# zigduino-r3a.net
KiCad netlist of a schematic drawn in EAGLE
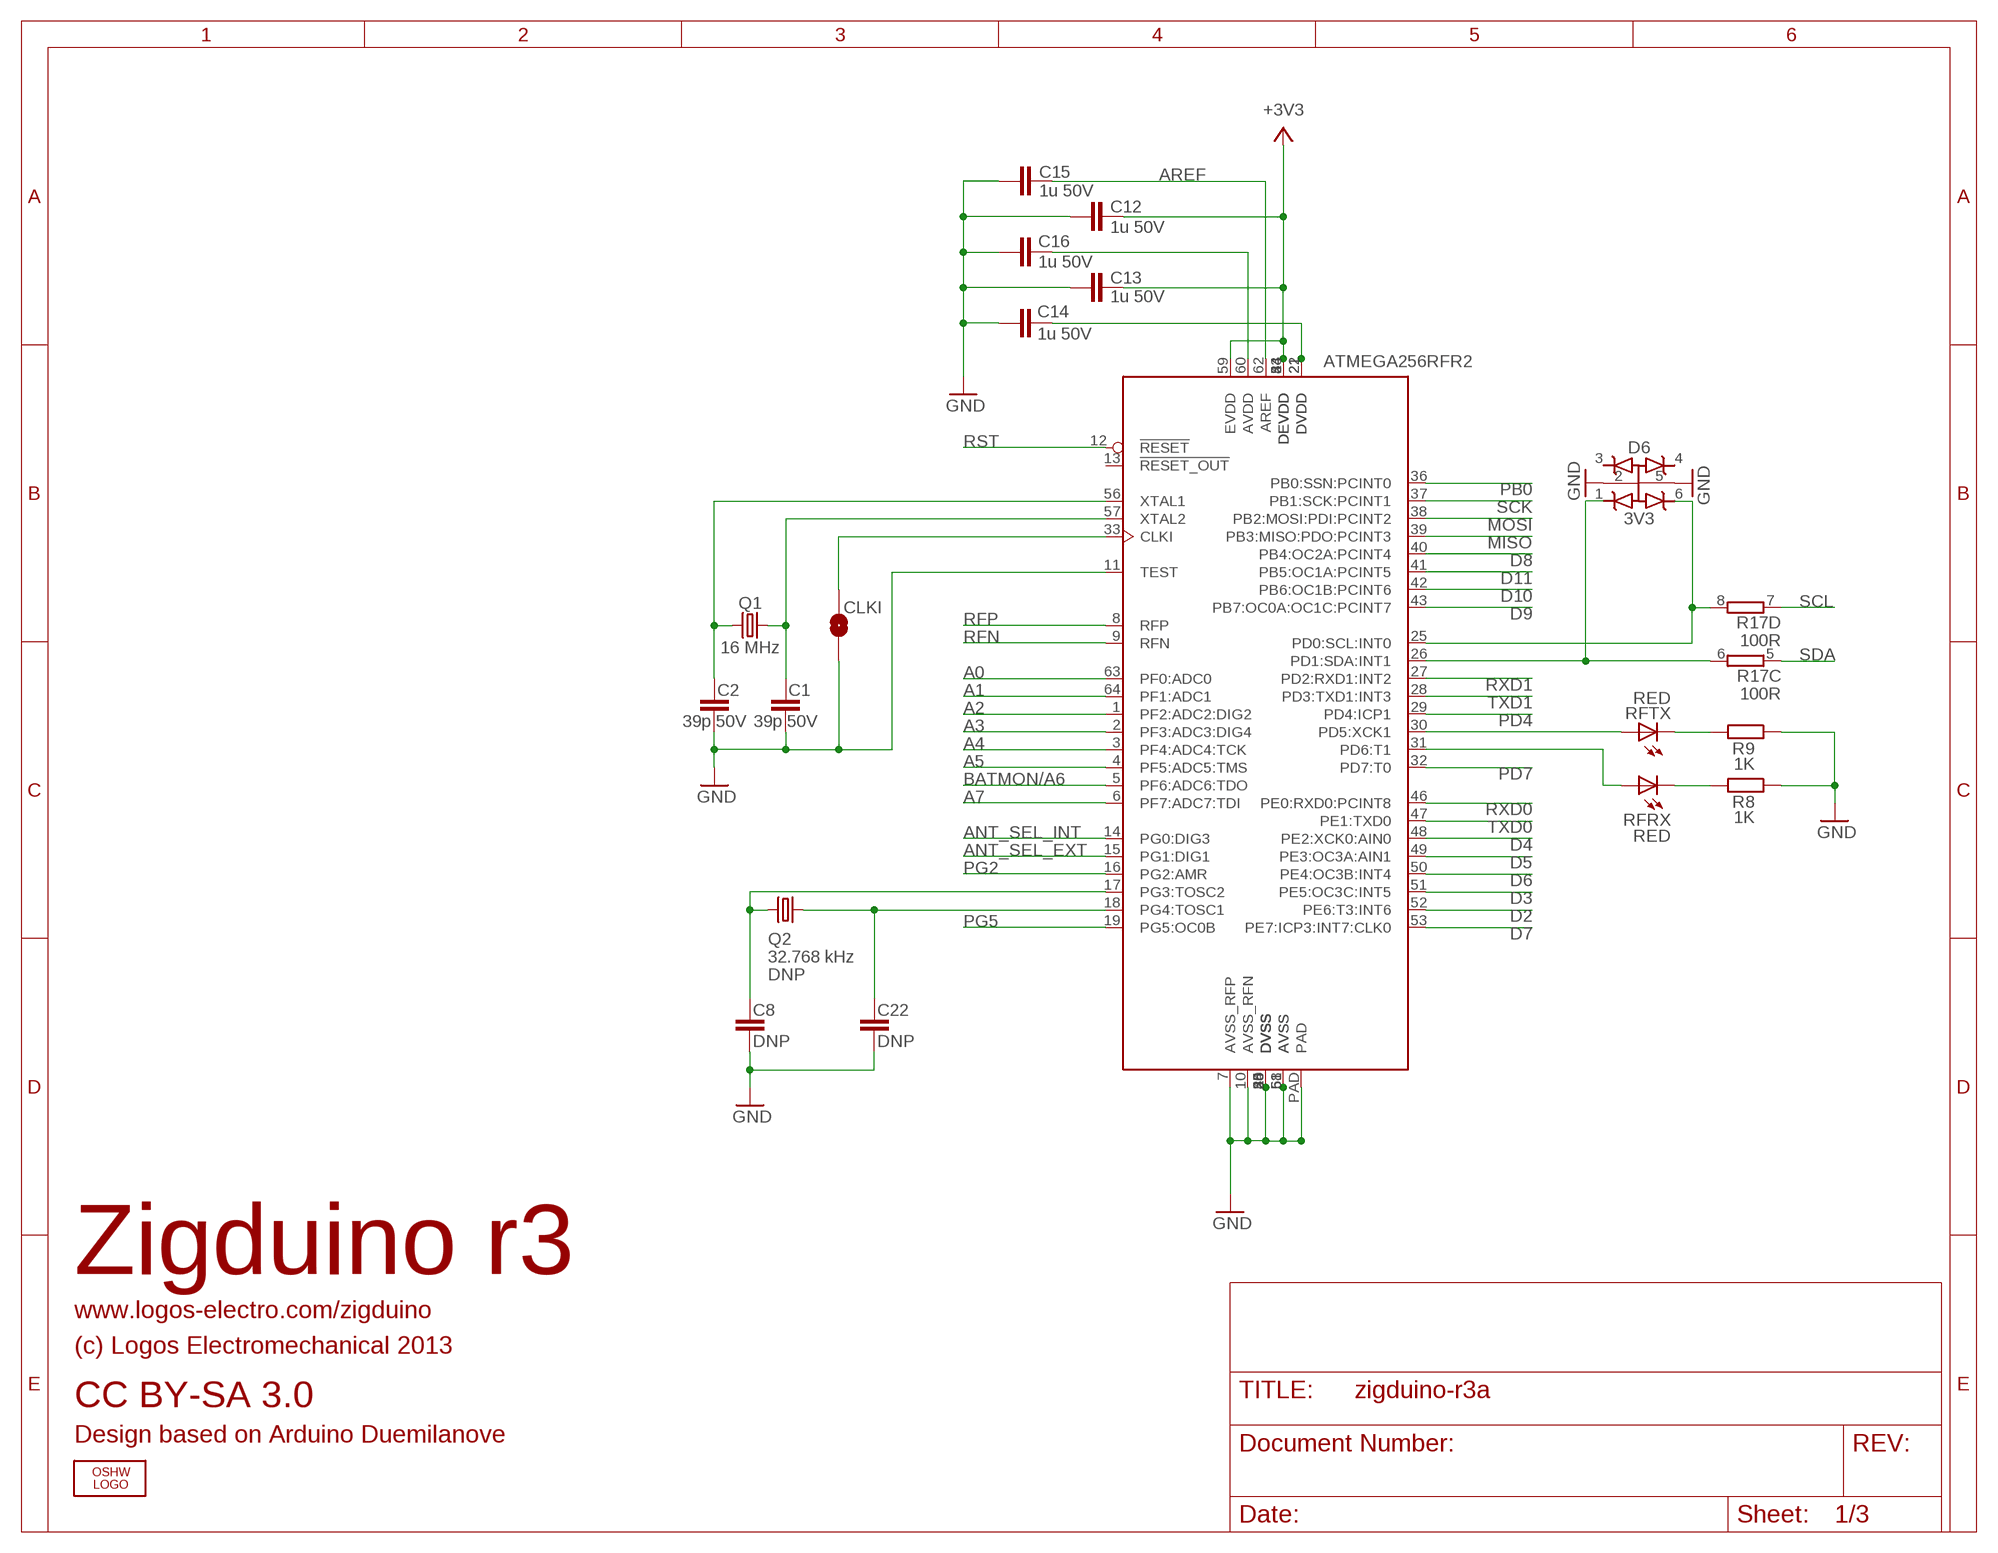
[diagram p0: schematic, sheet 1]
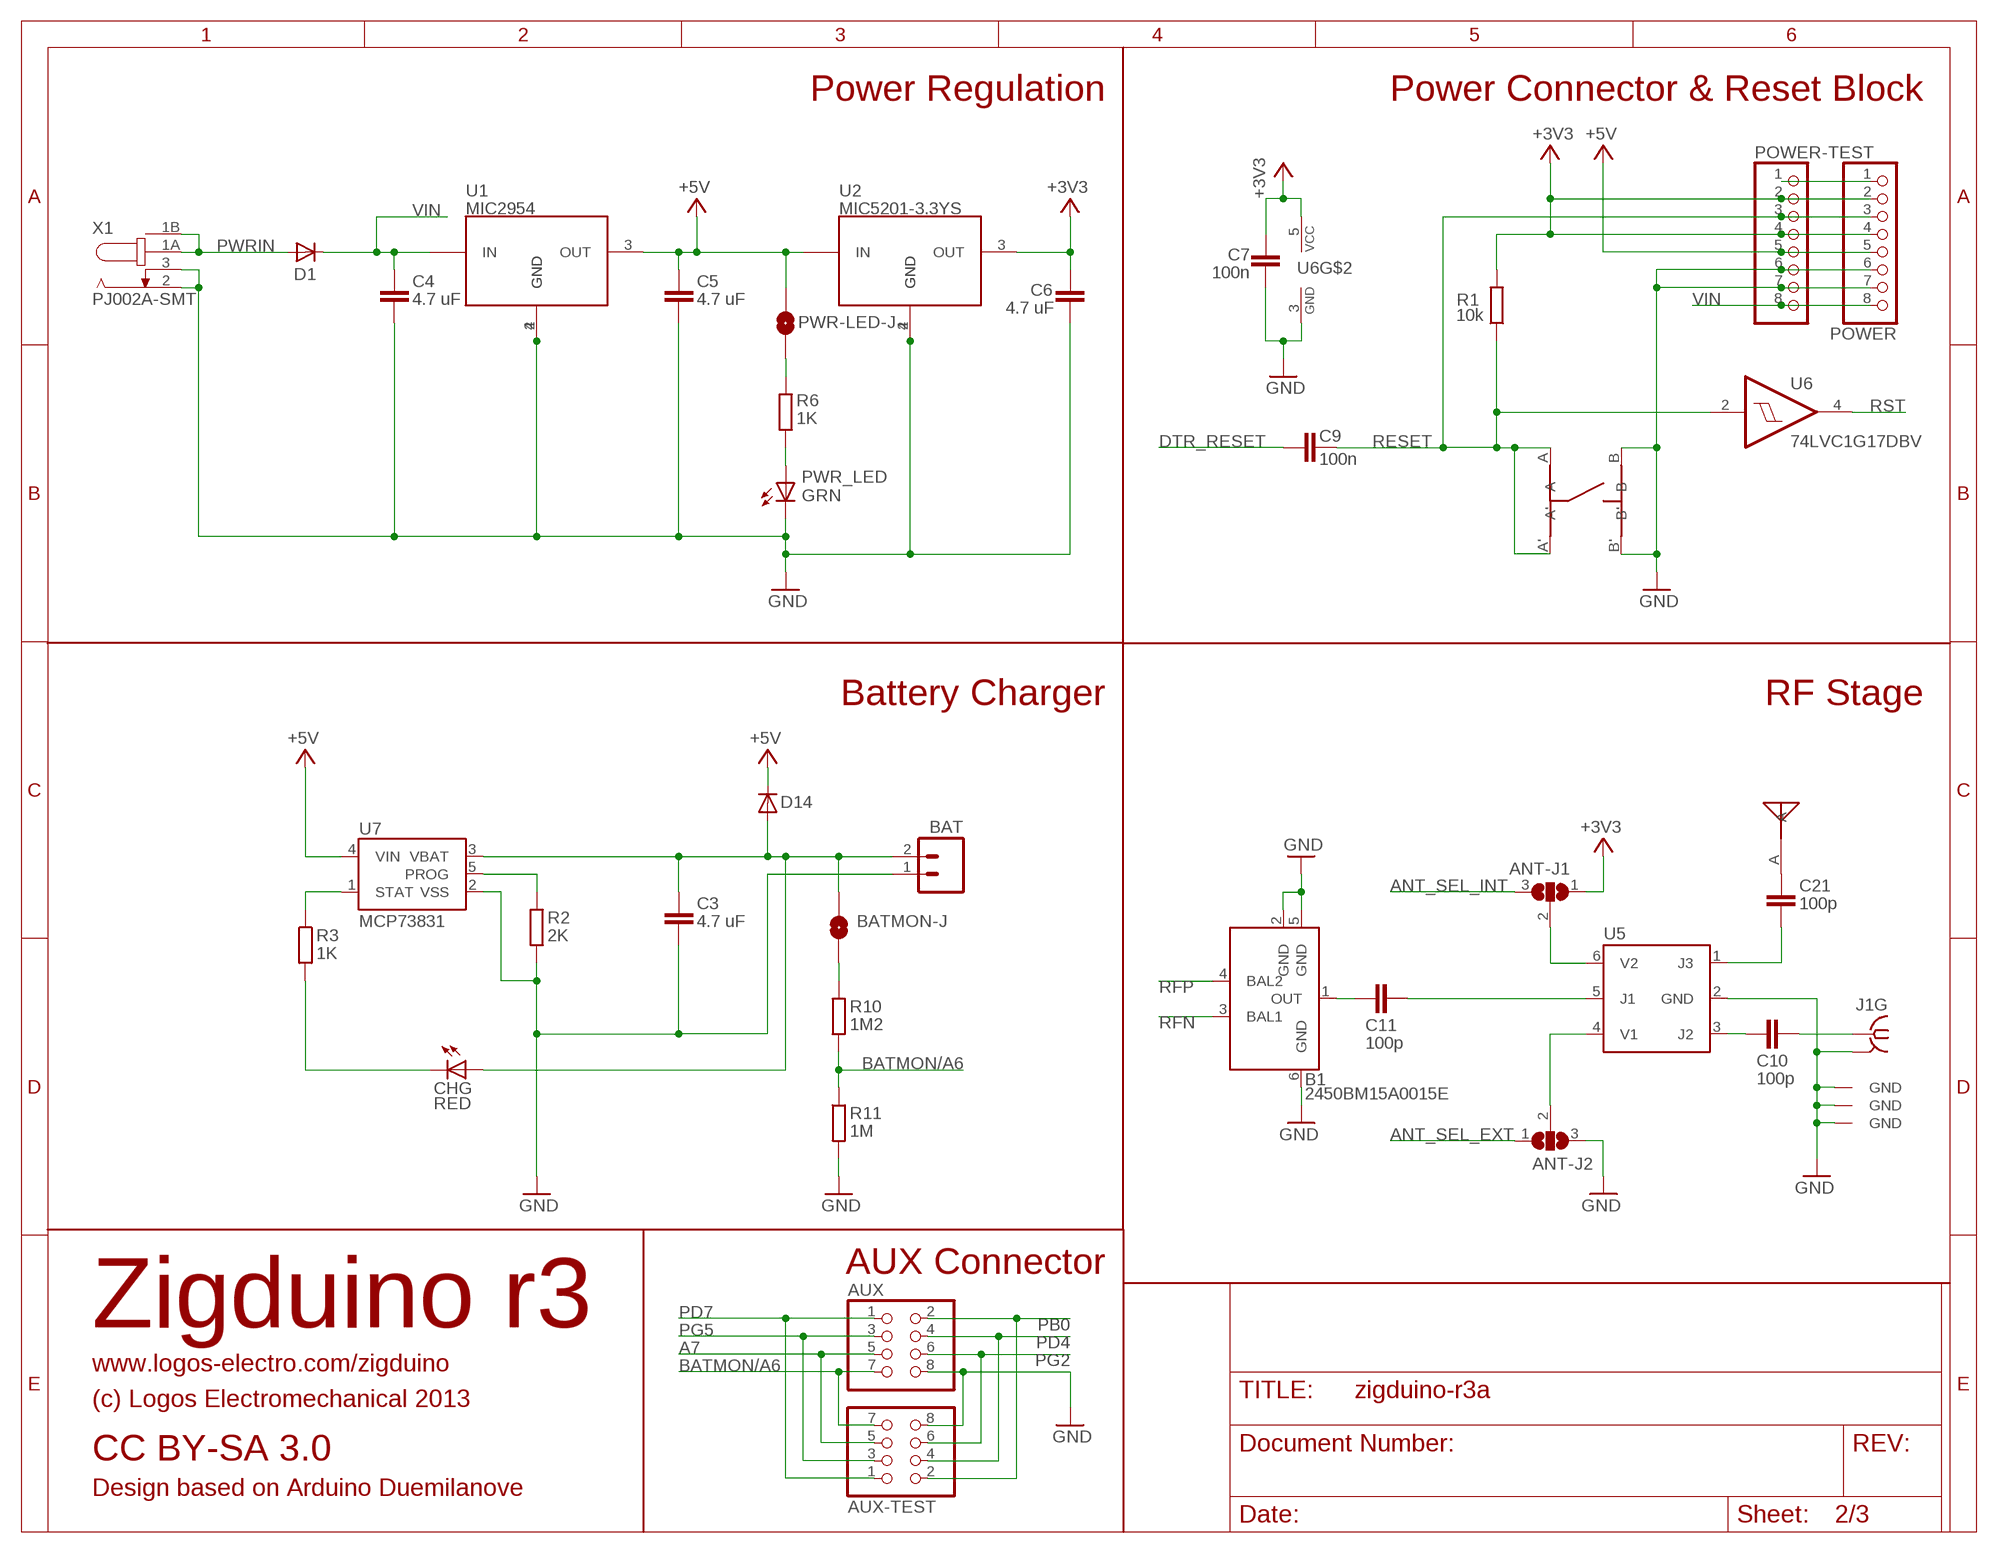
[diagram p1: schematic, sheet 2]
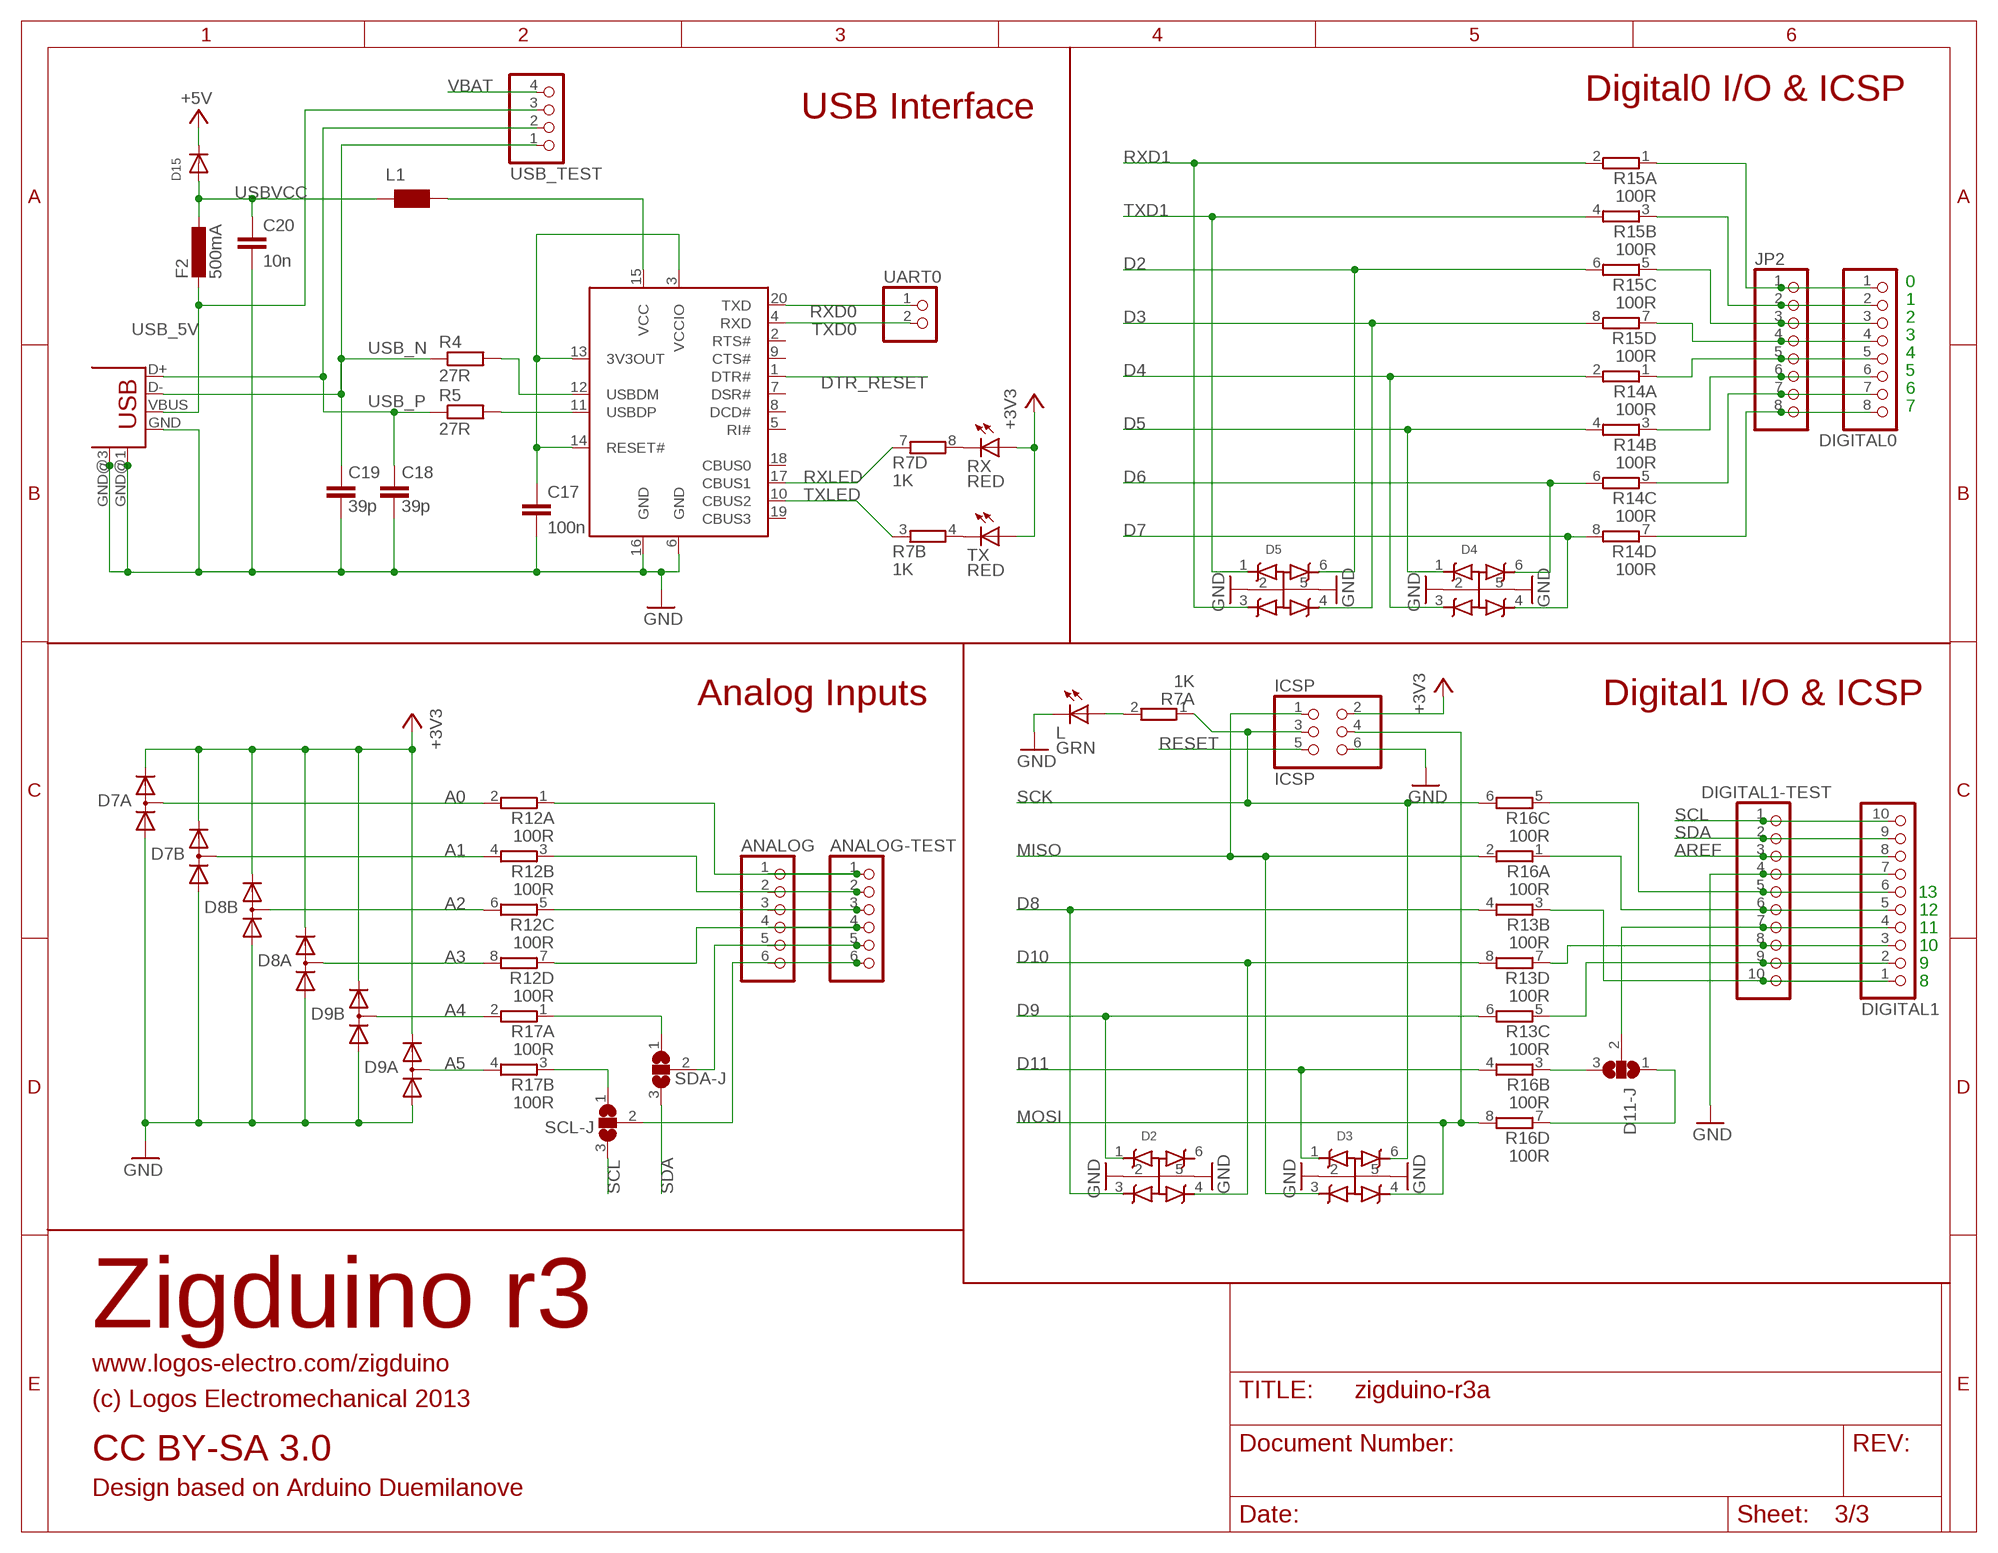
[diagram p2: schematic, sheet 3]

(export (version "E")
  (design (tool "Eeschema 10.0.6"))
  (components
    (comp (ref "ANT-J1")
      (value "SOLDERJUMPER_2WAYSHORT1&2")
      (footprint "eagle-import:SJ_3_SHORT1&2")
      (libsource (lib "eagle-import") (part "SOLDERJUMPER_2WAYSHORT1&2"))
    )
    (comp (ref "ANT-J2")
      (value "SOLDERJUMPER_2WAYSHORT2&3")
      (footprint "eagle-import:SJ_3_SHORT2&3")
      (libsource (lib "eagle-import") (part "SOLDERJUMPER_2WAYSHORT2&3"))
    )
    (comp (ref "ANT1")
      (value "MOLEX-ANT")
      (footprint "eagle-import:MOLEX-ANT")
      (fields (field (name "PARTNO") "0479480001"))
      (libsource (lib "eagle-import") (part "MOLEX-ANT"))
    )
    (comp (ref "AUX")
      (value "PINHD-2X4_2.54-SMD")
      (footprint "eagle-import:2X04SMD")
      (libsource (lib "eagle-import") (part "PINHD-2X4_2.54-SMD"))
    )
    (comp (ref "AUX-TEST")
      (value "PINHD-2X4TEST")
      (footprint "eagle-import:2X04-TEST")
      (libsource (lib "eagle-import") (part "PINHD-2X4TEST"))
    )
    (comp (ref "B1")
      (value "2450BM15A0015E")
      (footprint "eagle-import:WURTH-BALUN")
      (libsource (lib "eagle-import") (part "2450BM15A0015E"))
    )
    (comp (ref "BAT")
      (value "M02-JST-2MM-SMT")
      (footprint "eagle-import:S2B-PH")
      (fields (field (name "PARTNO") "S2B-PH-SM4-TB(LF)(SN)"))
      (libsource (lib "eagle-import") (part "M02-JST-2MM-SMT"))
    )
    (comp (ref "BATMON-J")
      (value "SOLDERJUMPERTRACE")
      (footprint "eagle-import:SJ_2S-TRACE")
      (libsource (lib "eagle-import") (part "SOLDERJUMPERTRACE"))
    )
    (comp (ref "C3")
      (value "4.7 uF")
      (footprint "eagle-import:C1206")
      (fields (field (name "PARTNO") "C3216Y5V1H475Z"))
      (libsource (lib "eagle-import") (part "C-EUC1206"))
    )
    (comp (ref "C4")
      (value "4.7 uF")
      (footprint "eagle-import:C1206")
      (fields (field (name "PARTNO") "C3216Y5V1H475Z"))
      (libsource (lib "eagle-import") (part "C-EUC1206"))
    )
    (comp (ref "C5")
      (value "4.7 uF")
      (footprint "eagle-import:C1206")
      (fields (field (name "PARTNO") "C3216Y5V1H475Z"))
      (libsource (lib "eagle-import") (part "C-EUC1206"))
    )
    (comp (ref "C6")
      (value "4.7 uF")
      (footprint "eagle-import:C1206")
      (fields (field (name "PARTNO") "C3216Y5V1H475Z"))
      (libsource (lib "eagle-import") (part "C-EUC1206"))
    )
    (comp (ref "C7")
      (value "100n")
      (footprint "eagle-import:C0603")
      (fields (field (name "PARTNO") "CC0603MRY5V9BB104"))
      (libsource (lib "eagle-import") (part "C-EUC0603"))
    )
    (comp (ref "C9")
      (value "100n")
      (footprint "eagle-import:C0603")
      (fields (field (name "PARTNO") "CC0603MRY5V9BB104"))
      (libsource (lib "eagle-import") (part "C-EUC0603"))
    )
    (comp (ref "C10")
      (value "100p")
      (footprint "eagle-import:C0603")
      (libsource (lib "eagle-import") (part "C-EUC0603"))
    )
    (comp (ref "C11")
      (value "100p")
      (footprint "eagle-import:C0603")
      (libsource (lib "eagle-import") (part "C-EUC0603"))
    )
    (comp (ref "C21")
      (value "100p")
      (footprint "eagle-import:C0603")
      (libsource (lib "eagle-import") (part "C-EUC0603"))
    )
    (comp (ref "CHG")
      (value "RED")
      (footprint "eagle-import:CHIP-LED0603")
      (fields (field (name "PARTNO") "LTST-C193KRKT-5A"))
      (libsource (lib "eagle-import") (part "LEDCHIP-LED0603"))
    )
    (comp (ref "D1")
      (value "DIODESOD-123")
      (footprint "eagle-import:SOD-123")
      (fields (field (name "PARTNO") "B150B-13-F"))
      (libsource (lib "eagle-import") (part "DIODESOD-123"))
    )
    (comp (ref "D14")
      (value "DIODESOD-123")
      (footprint "eagle-import:SOD-123")
      (fields (field (name "PARTNO") "B150B-13-F"))
      (libsource (lib "eagle-import") (part "DIODESOD-123"))
    )
    (comp (ref "J1")
      (value "CONNREVSMA003.062")
      (footprint "eagle-import:EDGE-RSMA")
      (libsource (lib "eagle-import") (part "CONNREVSMA003.062"))
    )
    (comp (ref "POWER")
      (value "PINHD-1X8_2.54-SMD")
      (footprint "eagle-import:1X08SMD")
      (fields (field (name "PARTNO") "19743"))
      (libsource (lib "eagle-import") (part "PINHD-1X8_2.54-SMD"))
    )
    (comp (ref "POWER-TEST")
      (value "PINHD-1X8TEST")
      (footprint "eagle-import:1X08-TEST")
      (libsource (lib "eagle-import") (part "PINHD-1X8TEST"))
    )
    (comp (ref "PWR-LED-J")
      (value "SOLDERJUMPERTRACE")
      (footprint "eagle-import:SJ_2S-TRACE")
      (libsource (lib "eagle-import") (part "SOLDERJUMPERTRACE"))
    )
    (comp (ref "PWR_LED")
      (value "GRN")
      (footprint "eagle-import:CHIP-LED0603")
      (fields (field (name "PARTNO") "LTST-C193KGKT-5A"))
      (libsource (lib "eagle-import") (part "LEDCHIP-LED0603"))
    )
    (comp (ref "R1")
      (value "10k")
      (footprint "eagle-import:R0603")
      (fields (field (name "PARTNO") "RMCF0603FT10K0"))
      (libsource (lib "eagle-import") (part "R-EU_R0603"))
    )
    (comp (ref "R2")
      (value "2K")
      (footprint "eagle-import:R0603")
      (fields (field (name "PARTNO") "RC0603FR-072KL"))
      (libsource (lib "eagle-import") (part "R-EU_R0603"))
    )
    (comp (ref "R3")
      (value "1K")
      (footprint "eagle-import:R0603")
      (fields (field (name "PARTNO") "RMCF0603FT1K00"))
      (libsource (lib "eagle-import") (part "R-EU_R0603"))
    )
    (comp (ref "R6")
      (value "1K")
      (footprint "eagle-import:R0603")
      (fields (field (name "PARTNO") "RMCF0603FT1K00"))
      (libsource (lib "eagle-import") (part "R-EU_R0603"))
    )
    (comp (ref "R10")
      (value "1M2")
      (footprint "eagle-import:R0603")
      (fields (field (name "PARTNO") "ERJ-3EKF1204V"))
      (libsource (lib "eagle-import") (part "R-EU_R0603"))
    )
    (comp (ref "R11")
      (value "1M")
      (footprint "eagle-import:R0603")
      (fields (field (name "PARTNO") "ERJ-3EKF1004V"))
      (libsource (lib "eagle-import") (part "R-EU_R0603"))
    )
    (comp (ref "SW1")
      (value "EVQ-PSD02K")
      (footprint "eagle-import:EVQPSD02K")
      (libsource (lib "eagle-import") (part "EVQ-PSD02K"))
    )
    (comp (ref "U1")
      (value "MIC2954")
      (footprint "eagle-import:SOT223")
      (fields (field (name "PARTNO") "MIC2954-03WS-TR"))
      (libsource (lib "eagle-import") (part "MIC2954"))
    )
    (comp (ref "U2")
      (value "MIC5201-3.3YS")
      (footprint "eagle-import:SOT223")
      (fields (field (name "PARTNO") "MIC5201-3.3YS TR"))
      (libsource (lib "eagle-import") (part "MIC5201-3.3BS"))
    )
    (comp (ref "U5")
      (value "AS222-92LF")
      (footprint "eagle-import:SC70-6L")
      (libsource (lib "eagle-import") (part "AS222-92LF"))
    )
    (comp (ref "U6")
      (value "74LVC1G17DBV")
      (footprint "eagle-import:SOT23-5")
      (fields (field (name "PARTNO") "SN74LVC1G17DBVR") (field (name "BOM") "INCLUDE"))
      (libsource (lib "eagle-import") (part "741G17DBVLVC"))
    )
    (comp (ref "U7")
      (value "MCP73831")
      (footprint "eagle-import:SOT23-5")
      (fields (field (name "PARTNO") "MCP73831T-2ACI/OT"))
      (libsource (lib "eagle-import") (part "MCP73831"))
    )
    (comp (ref "X1")
      (value "PJ002A-SMT")
      (footprint "eagle-import:PJ002A-SMT")
      (fields (field (name "PARTNO") "PJ-002AH-SMT"))
      (libsource (lib "eagle-import") (part "PJ002A-SMT"))
    )
    (comp (ref "ANALOG")
      (value "PINHD-1X6_2.54-SMD")
      (footprint "eagle-import:1X06SMD")
      (fields (field (name "PARTNO") "19742"))
      (libsource (lib "eagle-import") (part "PINHD-1X6_2.54-SMD"))
    )
    (comp (ref "ANALOG-TEST")
      (value "PINHD-1X6TEST")
      (footprint "eagle-import:1X06-TEST")
      (libsource (lib "eagle-import") (part "PINHD-1X6TEST"))
    )
    (comp (ref "C17")
      (value "100n")
      (footprint "eagle-import:C0603")
      (fields (field (name "PARTNO") "CC0603MRY5V9BB104"))
      (libsource (lib "eagle-import") (part "C-EUC0603"))
    )
    (comp (ref "C18")
      (value "39p")
      (footprint "eagle-import:C0603")
      (fields (field (name "PARTNO") "C1608C0G1H390J"))
      (libsource (lib "eagle-import") (part "C-EUC0603"))
    )
    (comp (ref "C19")
      (value "39p")
      (footprint "eagle-import:C0603")
      (fields (field (name "PARTNO") "C1608C0G1H390J"))
      (libsource (lib "eagle-import") (part "C-EUC0603"))
    )
    (comp (ref "C20")
      (value "10n")
      (footprint "eagle-import:C0603")
      (fields (field (name "PARTNO") "GRM188R71H103KA01D"))
      (libsource (lib "eagle-import") (part "C-EUC0603"))
    )
    (comp (ref "D2")
      (value "PESD3V3S4UD")
      (footprint "eagle-import:SC74_INFINEON")
      (libsource (lib "eagle-import") (part "PESD3V3S4UD"))
    )
    (comp (ref "D3")
      (value "PESD3V3S4UD")
      (footprint "eagle-import:SC74_INFINEON")
      (libsource (lib "eagle-import") (part "PESD3V3S4UD"))
    )
    (comp (ref "D4")
      (value "PESD3V3S4UD")
      (footprint "eagle-import:SC74_INFINEON")
      (libsource (lib "eagle-import") (part "PESD3V3S4UD"))
    )
    (comp (ref "D5")
      (value "PESD3V3S4UD")
      (footprint "eagle-import:SC74_INFINEON")
      (libsource (lib "eagle-import") (part "PESD3V3S4UD"))
    )
    (comp (ref "D7")
      (value "SD103ASDM")
      (footprint "eagle-import:SOT26")
      (fields
        (field (name "BOM") "INCLUDE")
        (field (name "PARTNO") "SD103ASDM-7")
        (field (name "VOLT") "40V")
      )
      (libsource (lib "eagle-import") (part "SD103ASDM"))
    )
    (comp (ref "D8")
      (value "SD103ASDM")
      (footprint "eagle-import:SOT26")
      (fields
        (field (name "PARTNO") "SD103ASDM-7")
        (field (name "BOM") "INCLUDE")
        (field (name "VOLT") "40V")
      )
      (libsource (lib "eagle-import") (part "SD103ASDM"))
    )
    (comp (ref "D9")
      (value "SD103ASDM")
      (footprint "eagle-import:SOT26")
      (fields
        (field (name "PARTNO") "SD103ASDM-7")
        (field (name "BOM") "INCLUDE")
        (field (name "VOLT") "40V")
      )
      (libsource (lib "eagle-import") (part "SD103ASDM"))
    )
    (comp (ref "D11-J")
      (value "SOLDERJUMPER_2WAYSHORT2&3")
      (footprint "eagle-import:SJ_3_SHORT2&3")
      (libsource (lib "eagle-import") (part "SOLDERJUMPER_2WAYSHORT2&3"))
    )
    (comp (ref "D15")
      (value "DIODESOD-123")
      (footprint "eagle-import:SOD-123")
      (fields (field (name "PARTNO") "B150B-13-F"))
      (libsource (lib "eagle-import") (part "DIODESOD-123"))
    )
    (comp (ref "DIGITAL0")
      (value "PINHD-1X8_2.54-SMD")
      (footprint "eagle-import:1X08SMD")
      (fields (field (name "PARTNO") "19743"))
      (libsource (lib "eagle-import") (part "PINHD-1X8_2.54-SMD"))
    )
    (comp (ref "DIGITAL1")
      (value "PINHD-1X10_2.54-SMD")
      (footprint "eagle-import:1X10SMD")
      (fields (field (name "PARTNO") "20083"))
      (libsource (lib "eagle-import") (part "PINHD-1X10_2.54-SMD"))
    )
    (comp (ref "DIGITAL1-TEST")
      (value "PINHD-1X10TEST")
      (footprint "eagle-import:1X10-TEST")
      (libsource (lib "eagle-import") (part "PINHD-1X10TEST"))
    )
    (comp (ref "F2")
      (value "500mA")
      (footprint "eagle-import:L1812")
      (fields (field (name "PARTNO") "MF-MSMF050-2"))
      (libsource (lib "eagle-import") (part "L-EUL1812"))
    )
    (comp (ref "ICSP")
      (value "ICSP")
      (footprint "eagle-import:2X03")
      (fields (field (name "PARTNO") "961206-6404-AR"))
      (libsource (lib "eagle-import") (part "PINHD-2X3"))
    )
    (comp (ref "JP2")
      (value "PINHD-1X8TEST")
      (footprint "eagle-import:1X08-TEST")
      (libsource (lib "eagle-import") (part "PINHD-1X8TEST"))
    )
    (comp (ref "L")
      (value "GRN")
      (footprint "eagle-import:CHIP-LED0603")
      (fields (field (name "PARTNO") "LTST-C193KGKT-5A"))
      (libsource (lib "eagle-import") (part "LEDCHIP-LED0603"))
    )
    (comp (ref "L1")
      (value "WE-CBF_0805")
      (footprint "eagle-import:0805")
      (fields (field (name "PARTNO") "MI0805K400R-10"))
      (libsource (lib "eagle-import") (part "WE-CBF_0805"))
    )
    (comp (ref "R4")
      (value "27R")
      (footprint "eagle-import:R0603")
      (fields (field (name "PARTNO") "RC0603JR-0727RL"))
      (libsource (lib "eagle-import") (part "R-EU_R0603"))
    )
    (comp (ref "R5")
      (value "27R")
      (footprint "eagle-import:R0603")
      (fields (field (name "PARTNO") "RC0603JR-0727RL"))
      (libsource (lib "eagle-import") (part "R-EU_R0603"))
    )
    (comp (ref "R7")
      (value "1K")
      (footprint "eagle-import:CTS742C083-RES")
      (fields (field (name "BOM") "INCLUDE") (field (name "PARTNO") "742C083102JPTR"))
      (libsource (lib "eagle-import") (part "4R-NCTS742C083"))
    )
    (comp (ref "R12")
      (value "100R")
      (footprint "eagle-import:CTS742C083-RES")
      (fields (field (name "BOM") "INCLUDE") (field (name "PARTNO") "742C083101JPTR"))
      (libsource (lib "eagle-import") (part "4R-NCTS742C083"))
    )
    (comp (ref "R13")
      (value "100R")
      (footprint "eagle-import:CTS742C083-RES")
      (fields (field (name "BOM") "INCLUDE") (field (name "PARTNO") "742C083101JPTR"))
      (libsource (lib "eagle-import") (part "4R-NCTS742C083"))
    )
    (comp (ref "R14")
      (value "100R")
      (footprint "eagle-import:CTS742C083-RES")
      (fields (field (name "BOM") "INCLUDE") (field (name "PARTNO") "742C083101JPTR"))
      (libsource (lib "eagle-import") (part "4R-NCTS742C083"))
    )
    (comp (ref "R15")
      (value "100R")
      (footprint "eagle-import:CTS742C083-RES")
      (fields (field (name "BOM") "INCLUDE") (field (name "PARTNO") "742C083101JPTR"))
      (libsource (lib "eagle-import") (part "4R-NCTS742C083"))
    )
    (comp (ref "R16")
      (value "100R")
      (footprint "eagle-import:CTS742C083-RES")
      (fields (field (name "BOM") "INCLUDE") (field (name "PARTNO") "742C083101JPTR"))
      (libsource (lib "eagle-import") (part "4R-NCTS742C083"))
    )
    (comp (ref "R17")
      (value "100R")
      (footprint "eagle-import:CTS742C083-RES")
      (fields (field (name "PARTNO") "742C083101JPTR") (field (name "BOM") "INCLUDE"))
      (libsource (lib "eagle-import") (part "4R-NCTS742C083"))
    )
    (comp (ref "RX")
      (value "RED")
      (footprint "eagle-import:CHIP-LED0603")
      (fields (field (name "PARTNO") "LTST-C193KRKT-5A"))
      (libsource (lib "eagle-import") (part "LEDCHIP-LED0603"))
    )
    (comp (ref "SCL-J")
      (value "SOLDERJUMPER_2WAYSHORT2&3")
      (footprint "eagle-import:SJ_3_SHORT2&3")
      (libsource (lib "eagle-import") (part "SOLDERJUMPER_2WAYSHORT2&3"))
    )
    (comp (ref "SDA-J")
      (value "SOLDERJUMPER_2WAYSHORT2&3")
      (footprint "eagle-import:SJ_3_SHORT2&3")
      (libsource (lib "eagle-import") (part "SOLDERJUMPER_2WAYSHORT2&3"))
    )
    (comp (ref "TX")
      (value "RED")
      (footprint "eagle-import:CHIP-LED0603")
      (fields (field (name "PARTNO") "LTST-C193KRKT-5A"))
      (libsource (lib "eagle-import") (part "LEDCHIP-LED0603"))
    )
    (comp (ref "U4")
      (value "FT231XS-R")
      (footprint "eagle-import:SSOP20")
      (libsource (lib "eagle-import") (part "FT231XS-R"))
    )
    (comp (ref "UART0")
      (value "PINHD-1X2")
      (footprint "eagle-import:1X02")
      (fields (field (name "PARTNO") "00522"))
      (libsource (lib "eagle-import") (part "PINHD-1X2"))
    )
    (comp (ref "USB")
      (value "USB-MB-S")
      (footprint "eagle-import:USB-MB-S")
      (fields (field (name "PARTNO") "20236"))
      (libsource (lib "eagle-import") (part "USB-MB-S"))
    )
    (comp (ref "USB_TEST")
      (value "PINHD-1X4TEST")
      (footprint "eagle-import:1X04-TEST")
      (libsource (lib "eagle-import") (part "PINHD-1X4TEST"))
    )
    (comp (ref "C1")
      (value "39p 50V")
      (footprint "eagle-import:C0603")
      (fields (field (name "PARTNO") "C1608C0G1H390J"))
      (libsource (lib "eagle-import") (part "C-EUC0603"))
    )
    (comp (ref "C2")
      (value "39p 50V")
      (footprint "eagle-import:C0603")
      (fields (field (name "PARTNO") "C1608C0G1H390J"))
      (libsource (lib "eagle-import") (part "C-EUC0603"))
    )
    (comp (ref "C8")
      (value "DNP")
      (footprint "eagle-import:C0603")
      (libsource (lib "eagle-import") (part "C-EUC0603"))
    )
    (comp (ref "C12")
      (value "1u 50V")
      (footprint "eagle-import:C0603")
      (libsource (lib "eagle-import") (part "C-EUC0603"))
    )
    (comp (ref "C13")
      (value "1u 50V")
      (footprint "eagle-import:C0603")
      (libsource (lib "eagle-import") (part "C-EUC0603"))
    )
    (comp (ref "C14")
      (value "1u 50V")
      (footprint "eagle-import:C0603")
      (libsource (lib "eagle-import") (part "C-EUC0603"))
    )
    (comp (ref "C15")
      (value "1u 50V")
      (footprint "eagle-import:C0603")
      (libsource (lib "eagle-import") (part "C-EUC0603"))
    )
    (comp (ref "C16")
      (value "1u 50V")
      (footprint "eagle-import:C0603")
      (libsource (lib "eagle-import") (part "C-EUC0603"))
    )
    (comp (ref "C22")
      (value "DNP")
      (footprint "eagle-import:C0603")
      (libsource (lib "eagle-import") (part "C-EUC0603"))
    )
    (comp (ref "CLKI")
      (value "SOLDERJUMPERTRACE")
      (footprint "eagle-import:SJ_2S-TRACE")
      (libsource (lib "eagle-import") (part "SOLDERJUMPERTRACE"))
    )
    (comp (ref "D6")
      (value "3V3")
      (footprint "eagle-import:SC74_INFINEON")
      (libsource (lib "eagle-import") (part "PESD3V3S4UD"))
    )
    (comp (ref "LOGO1")
      (value "OSHW_LOGO_FILLX0200-NT")
      (footprint "eagle-import:OSHW_FILLX200_NOTEXT")
      (libsource (lib "eagle-import") (part "OSHW_LOGO_FILLX0200-NT"))
    )
    (comp (ref "Q1")
      (value "16 MHz")
      (footprint "eagle-import:CSM-3X")
      (fields (field (name "PARTNO") "ECS-160-20-3X-TR"))
      (libsource (lib "eagle-import") (part "CRYSTALCSM-3X"))
    )
    (comp (ref "Q2")
      (value "32.768 kHz")
      (footprint "eagle-import:TC26H")
      (libsource (lib "eagle-import") (part "CRYSTALTC26H"))
    )
    (comp (ref "R8")
      (value "1K")
      (footprint "eagle-import:R0603")
      (fields (field (name "PARTNO") "RMCF0603FT1K00"))
      (libsource (lib "eagle-import") (part "R-EU_R0603"))
    )
    (comp (ref "R9")
      (value "1K")
      (footprint "eagle-import:R0603")
      (fields (field (name "PARTNO") "RMCF0603FT1K00"))
      (libsource (lib "eagle-import") (part "R-EU_R0603"))
    )
    (comp (ref "RFRX")
      (value "RED")
      (footprint "eagle-import:CHIP-LED0603")
      (fields (field (name "PARTNO") "LTST-C193KRKT-5A"))
      (libsource (lib "eagle-import") (part "LEDCHIP-LED0603"))
    )
    (comp (ref "RFTX")
      (value "RED")
      (footprint "eagle-import:CHIP-LED0603")
      (fields (field (name "PARTNO") "LTST-C193KRKT-5A"))
      (libsource (lib "eagle-import") (part "LEDCHIP-LED0603"))
    )
    (comp (ref "U3")
      (value "ATMEGA128RFA1")
      (footprint "eagle-import:QFN64")
      (fields (field (name "PARTNO") "ATMEGA128RFA1-ZUR"))
      (libsource (lib "eagle-import") (part "ATMEGA128RFA1"))
    )
  )
  (nets
    (net (code "1") (name "+3V3") (class "Default")
      (node (ref "ANT-J1") (pin "1") (pinfunction "1_1") (pintype "passive"))
      (node (ref "C12") (pin "1") (pinfunction "1_1") (pintype "passive"))
      (node (ref "C13") (pin "1") (pinfunction "1_1") (pintype "passive"))
      (node (ref "C6") (pin "1") (pinfunction "1_1") (pintype "passive"))
      (node (ref "C7") (pin "2") (pinfunction "2_2") (pintype "passive"))
      (node (ref "D7") (pin "2") (pinfunction "C_2") (pintype "passive"))
      (node (ref "D7") (pin "5") (pinfunction "C_5") (pintype "passive"))
      (node (ref "D8") (pin "2") (pinfunction "C_2") (pintype "passive"))
      (node (ref "D8") (pin "5") (pinfunction "C_5") (pintype "passive"))
      (node (ref "D9") (pin "2") (pinfunction "C_2") (pintype "passive"))
      (node (ref "D9") (pin "5") (pinfunction "C_5") (pintype "passive"))
      (node (ref "ICSP") (pin "2") (pinfunction "2_2") (pintype "passive"))
      (node (ref "POWER") (pin "2") (pinfunction "2_2") (pintype "passive"))
      (node (ref "POWER") (pin "4") (pinfunction "4_4") (pintype "passive"))
      (node (ref "POWER-TEST") (pin "2") (pinfunction "2_2") (pintype "passive"))
      (node (ref "POWER-TEST") (pin "4") (pinfunction "4_4") (pintype "passive"))
      (node (ref "R1") (pin "2") (pinfunction "2_2") (pintype "passive"))
      (node (ref "RX") (pin "A") (pinfunction "A_A") (pintype "passive"))
      (node (ref "TX") (pin "A") (pinfunction "A_A") (pintype "passive"))
      (node (ref "U2") (pin "3") (pinfunction "OUT_3") (pintype "bidirectional"))
      (node (ref "U3") (pin "23") (pinfunction "DEVDD_23") (pintype "bidirectional"))
      (node (ref "U3") (pin "34") (pinfunction "DEVDD_34") (pintype "bidirectional"))
      (node (ref "U3") (pin "44") (pinfunction "DEVDD_44") (pintype "bidirectional"))
      (node (ref "U3") (pin "54") (pinfunction "DEVDD_54") (pintype "bidirectional"))
      (node (ref "U3") (pin "59") (pinfunction "EVDD_59") (pintype "bidirectional"))
      (node (ref "U6") (pin "5") (pinfunction "VCC_5") (pintype "power_in"))
    )
    (net (code "2") (name "+5V") (class "Default")
      (node (ref "C5") (pin "1") (pinfunction "1_1") (pintype "passive"))
      (node (ref "D14") (pin "C") (pinfunction "C_C") (pintype "passive"))
      (node (ref "D15") (pin "C") (pinfunction "C_C") (pintype "passive"))
      (node (ref "POWER") (pin "5") (pinfunction "5_5") (pintype "passive"))
      (node (ref "POWER-TEST") (pin "5") (pinfunction "5_5") (pintype "passive"))
      (node (ref "PWR-LED-J") (pin "2") (pinfunction "2_2") (pintype "passive"))
      (node (ref "U1") (pin "3") (pinfunction "OUT_3") (pintype "bidirectional"))
      (node (ref "U2") (pin "1") (pinfunction "IN_1") (pintype "bidirectional"))
      (node (ref "U7") (pin "4") (pinfunction "VIN_4") (pintype "power_in"))
    )
    (net (code "3") (name "A0") (class "Default")
      (node (ref "D7") (pin "4") (pinfunction "AC_4") (pintype "passive"))
      (node (ref "R12") (pin "2") (pinfunction "2_2") (pintype "passive"))
      (node (ref "U3") (pin "63") (pinfunction "PF0:ADC0_63") (pintype "bidirectional"))
    )
    (net (code "4") (name "A1") (class "Default")
      (node (ref "D7") (pin "1") (pinfunction "AC_1") (pintype "passive"))
      (node (ref "R12") (pin "4") (pinfunction "2_4") (pintype "passive"))
      (node (ref "U3") (pin "64") (pinfunction "PF1:ADC1_64") (pintype "bidirectional"))
    )
    (net (code "5") (name "A2") (class "Default")
      (node (ref "D8") (pin "1") (pinfunction "AC_1") (pintype "passive"))
      (node (ref "R12") (pin "6") (pinfunction "2_6") (pintype "passive"))
      (node (ref "U3") (pin "1") (pinfunction "PF2:ADC2:DIG2_1") (pintype "bidirectional"))
    )
    (net (code "6") (name "A3") (class "Default")
      (node (ref "D8") (pin "4") (pinfunction "AC_4") (pintype "passive"))
      (node (ref "R12") (pin "8") (pinfunction "2_8") (pintype "passive"))
      (node (ref "U3") (pin "2") (pinfunction "PF3:ADC3:DIG4_2") (pintype "bidirectional"))
    )
    (net (code "7") (name "A4") (class "Default")
      (node (ref "D9") (pin "1") (pinfunction "AC_1") (pintype "passive"))
      (node (ref "R17") (pin "2") (pinfunction "2_2") (pintype "passive"))
      (node (ref "U3") (pin "3") (pinfunction "PF4:ADC4:TCK_3") (pintype "bidirectional"))
    )
    (net (code "8") (name "A5") (class "Default")
      (node (ref "D9") (pin "4") (pinfunction "AC_4") (pintype "passive"))
      (node (ref "R17") (pin "4") (pinfunction "2_4") (pintype "passive"))
      (node (ref "U3") (pin "4") (pinfunction "PF5:ADC5:TMS_4") (pintype "bidirectional"))
    )
    (net (code "9") (name "A7") (class "Default")
      (node (ref "AUX") (pin "5") (pinfunction "5_5") (pintype "passive"))
      (node (ref "AUX-TEST") (pin "5") (pinfunction "5_5") (pintype "passive"))
      (node (ref "U3") (pin "6") (pinfunction "PF7:ADC7:TDI_6") (pintype "bidirectional"))
    )
    (net (code "10") (name "ANT_SEL_EXT") (class "Default")
      (node (ref "ANT-J2") (pin "1") (pinfunction "1_1") (pintype "passive"))
      (node (ref "U3") (pin "15") (pinfunction "PG1:DIG1_15") (pintype "bidirectional"))
    )
    (net (code "11") (name "ANT_SEL_INT") (class "Default")
      (node (ref "ANT-J1") (pin "3") (pinfunction "3_3") (pintype "passive"))
      (node (ref "U3") (pin "14") (pinfunction "PG0:DIG3_14") (pintype "bidirectional"))
    )
    (net (code "12") (name "AREF") (class "Default")
      (node (ref "C15") (pin "2") (pinfunction "2_2") (pintype "passive"))
      (node (ref "DIGITAL1") (pin "8") (pinfunction "8_8") (pintype "passive"))
      (node (ref "DIGITAL1-TEST") (pin "3") (pinfunction "3_3") (pintype "passive"))
      (node (ref "U3") (pin "62") (pinfunction "AREF_62") (pintype "bidirectional"))
    )
    (net (code "13") (name "BATMON{slash}A6") (class "Default")
      (node (ref "AUX") (pin "7") (pinfunction "7_7") (pintype "passive"))
      (node (ref "AUX-TEST") (pin "7") (pinfunction "7_7") (pintype "passive"))
      (node (ref "R10") (pin "2") (pinfunction "2_2") (pintype "passive"))
      (node (ref "R11") (pin "1") (pinfunction "1_1") (pintype "passive"))
      (node (ref "U3") (pin "5") (pinfunction "PF6:ADC6:TDO_5") (pintype "bidirectional"))
    )
    (net (code "14") (name "D2") (class "Default")
      (node (ref "D5") (pin "6") (pinfunction "Z6_6") (pintype "bidirectional"))
      (node (ref "R15") (pin "6") (pinfunction "2_6") (pintype "passive"))
      (node (ref "U3") (pin "52") (pinfunction "PE6:T3:INT6_52") (pintype "bidirectional"))
    )
    (net (code "15") (name "D3") (class "Default")
      (node (ref "D5") (pin "4") (pinfunction "Z4_4") (pintype "bidirectional"))
      (node (ref "R15") (pin "8") (pinfunction "2_8") (pintype "passive"))
      (node (ref "U3") (pin "51") (pinfunction "PE5:OC3C:INT5_51") (pintype "bidirectional"))
    )
    (net (code "16") (name "D4") (class "Default")
      (node (ref "D4") (pin "3") (pinfunction "Z3_3") (pintype "bidirectional"))
      (node (ref "R14") (pin "2") (pinfunction "2_2") (pintype "passive"))
      (node (ref "U3") (pin "48") (pinfunction "PE2:XCK0:AIN0_48") (pintype "bidirectional"))
    )
    (net (code "17") (name "D5") (class "Default")
      (node (ref "D4") (pin "1") (pinfunction "Z1_1") (pintype "bidirectional"))
      (node (ref "R14") (pin "4") (pinfunction "2_4") (pintype "passive"))
      (node (ref "U3") (pin "49") (pinfunction "PE3:OC3A:AIN1_49") (pintype "bidirectional"))
    )
    (net (code "18") (name "D6") (class "Default")
      (node (ref "D4") (pin "6") (pinfunction "Z6_6") (pintype "bidirectional"))
      (node (ref "R14") (pin "6") (pinfunction "2_6") (pintype "passive"))
      (node (ref "U3") (pin "50") (pinfunction "PE4:OC3B:INT4_50") (pintype "bidirectional"))
    )
    (net (code "19") (name "D7") (class "Default")
      (node (ref "D4") (pin "4") (pinfunction "Z4_4") (pintype "bidirectional"))
      (node (ref "R14") (pin "8") (pinfunction "2_8") (pintype "passive"))
      (node (ref "U3") (pin "53") (pinfunction "PE7:ICP3:INT7:CLK0_53") (pintype "bidirectional"))
    )
    (net (code "20") (name "D8") (class "Default")
      (node (ref "D2") (pin "3") (pinfunction "Z3_3") (pintype "bidirectional"))
      (node (ref "R13") (pin "4") (pinfunction "2_4") (pintype "passive"))
      (node (ref "U3") (pin "40") (pinfunction "PB4:OC2A:PCINT4_40") (pintype "bidirectional"))
    )
    (net (code "21") (name "D9") (class "Default")
      (node (ref "D2") (pin "1") (pinfunction "Z1_1") (pintype "bidirectional"))
      (node (ref "R13") (pin "6") (pinfunction "2_6") (pintype "passive"))
      (node (ref "U3") (pin "43") (pinfunction "PB7:OC0A:OC1C:PCINT7_43") (pintype "bidirectional"))
    )
    (net (code "22") (name "D10") (class "Default")
      (node (ref "D2") (pin "4") (pinfunction "Z4_4") (pintype "bidirectional"))
      (node (ref "R13") (pin "8") (pinfunction "2_8") (pintype "passive"))
      (node (ref "U3") (pin "42") (pinfunction "PB6:OC1B:PCINT6_42") (pintype "bidirectional"))
    )
    (net (code "23") (name "D11") (class "Default")
      (node (ref "D3") (pin "1") (pinfunction "Z1_1") (pintype "bidirectional"))
      (node (ref "R16") (pin "4") (pinfunction "2_4") (pintype "passive"))
      (node (ref "U3") (pin "41") (pinfunction "PB5:OC1A:PCINT5_41") (pintype "bidirectional"))
    )
    (net (code "24") (name "DTR_RESET") (class "Default")
      (node (ref "C9") (pin "1") (pinfunction "1_1") (pintype "passive"))
      (node (ref "U4") (pin "1") (pinfunction "DTR#_1") (pintype "bidirectional"))
    )
    (net (code "25") (name "GND") (class "Default")
      (node (ref "ANT-J2") (pin "3") (pinfunction "3_3") (pintype "passive"))
      (node (ref "AUX") (pin "8") (pinfunction "8_8") (pintype "passive"))
      (node (ref "AUX-TEST") (pin "8") (pinfunction "8_8") (pintype "passive"))
      (node (ref "B1") (pin "2") (pinfunction "GND_2") (pintype "bidirectional"))
      (node (ref "B1") (pin "5") (pinfunction "GND_5") (pintype "bidirectional"))
      (node (ref "B1") (pin "6") (pinfunction "GND_6") (pintype "bidirectional"))
      (node (ref "BAT") (pin "1") (pinfunction "1_1") (pintype "passive"))
      (node (ref "C1") (pin "1") (pinfunction "1_1") (pintype "passive"))
      (node (ref "C12") (pin "2") (pinfunction "2_2") (pintype "passive"))
      (node (ref "C13") (pin "2") (pinfunction "2_2") (pintype "passive"))
      (node (ref "C14") (pin "2") (pinfunction "2_2") (pintype "passive"))
      (node (ref "C15") (pin "1") (pinfunction "1_1") (pintype "passive"))
      (node (ref "C16") (pin "1") (pinfunction "1_1") (pintype "passive"))
      (node (ref "C17") (pin "2") (pinfunction "2_2") (pintype "passive"))
      (node (ref "C18") (pin "2") (pinfunction "2_2") (pintype "passive"))
      (node (ref "C19") (pin "2") (pinfunction "2_2") (pintype "passive"))
      (node (ref "C2") (pin "1") (pinfunction "1_1") (pintype "passive"))
      (node (ref "C20") (pin "2") (pinfunction "2_2") (pintype "passive"))
      (node (ref "C22") (pin "1") (pinfunction "1_1") (pintype "passive"))
      (node (ref "C3") (pin "2") (pinfunction "2_2") (pintype "passive"))
      (node (ref "C4") (pin "2") (pinfunction "2_2") (pintype "passive"))
      (node (ref "C5") (pin "2") (pinfunction "2_2") (pintype "passive"))
      (node (ref "C6") (pin "2") (pinfunction "2_2") (pintype "passive"))
      (node (ref "C7") (pin "1") (pinfunction "1_1") (pintype "passive"))
      (node (ref "C8") (pin "1") (pinfunction "1_1") (pintype "passive"))
      (node (ref "CLKI") (pin "2") (pinfunction "2_2") (pintype "passive"))
      (node (ref "D2") (pin "2") (pinfunction "G2_2") (pintype "bidirectional"))
      (node (ref "D2") (pin "5") (pinfunction "G5_5") (pintype "bidirectional"))
      (node (ref "D3") (pin "2") (pinfunction "G2_2") (pintype "bidirectional"))
      (node (ref "D3") (pin "5") (pinfunction "G5_5") (pintype "bidirectional"))
      (node (ref "D4") (pin "2") (pinfunction "G2_2") (pintype "bidirectional"))
      (node (ref "D4") (pin "5") (pinfunction "G5_5") (pintype "bidirectional"))
      (node (ref "D5") (pin "2") (pinfunction "G2_2") (pintype "bidirectional"))
      (node (ref "D5") (pin "5") (pinfunction "G5_5") (pintype "bidirectional"))
      (node (ref "D6") (pin "2") (pinfunction "G2_2") (pintype "bidirectional"))
      (node (ref "D6") (pin "5") (pinfunction "G5_5") (pintype "bidirectional"))
      (node (ref "D7") (pin "3") (pinfunction "A_3") (pintype "passive"))
      (node (ref "D7") (pin "6") (pinfunction "A_6") (pintype "passive"))
      (node (ref "D8") (pin "3") (pinfunction "A_3") (pintype "passive"))
      (node (ref "D8") (pin "6") (pinfunction "A_6") (pintype "passive"))
      (node (ref "D9") (pin "3") (pinfunction "A_3") (pintype "passive"))
      (node (ref "D9") (pin "6") (pinfunction "A_6") (pintype "passive"))
      (node (ref "DIGITAL1") (pin "7") (pinfunction "7_7") (pintype "passive"))
      (node (ref "DIGITAL1-TEST") (pin "4") (pinfunction "4_4") (pintype "passive"))
      (node (ref "ICSP") (pin "6") (pinfunction "6_6") (pintype "passive"))
      (node (ref "J1") (pin "SHIELD@0") (pinfunction "GND_SHIELD@0") (pintype "power_in"))
      (node (ref "J1") (pin "SHIELD@1") (pinfunction "GND_SHIELD@1") (pintype "power_in"))
      (node (ref "J1") (pin "SHIELD@2") (pinfunction "GND_SHIELD@2") (pintype "power_in"))
      (node (ref "J1") (pin "SHIELD@3") (pinfunction "GND_SHIELD@3") (pintype "power_in"))
      (node (ref "L") (pin "C") (pinfunction "C_C") (pintype "passive"))
      (node (ref "POWER") (pin "6") (pinfunction "6_6") (pintype "passive"))
      (node (ref "POWER") (pin "7") (pinfunction "7_7") (pintype "passive"))
      (node (ref "POWER-TEST") (pin "6") (pinfunction "6_6") (pintype "passive"))
      (node (ref "POWER-TEST") (pin "7") (pinfunction "7_7") (pintype "passive"))
      (node (ref "PWR_LED") (pin "C") (pinfunction "C_C") (pintype "passive"))
      (node (ref "R11") (pin "2") (pinfunction "2_2") (pintype "passive"))
      (node (ref "R2") (pin "1") (pinfunction "1_1") (pintype "passive"))
      (node (ref "R8") (pin "1") (pinfunction "1_1") (pintype "passive"))
      (node (ref "R9") (pin "1") (pinfunction "1_1") (pintype "passive"))
      (node (ref "SW1") (pin "B") (pinfunction "B_B") (pintype "bidirectional"))
      (node (ref "SW1") (pin "B'") (pinfunction "B'_B'") (pintype "bidirectional"))
      (node (ref "U1") (pin "2") (pinfunction "GND_2") (pintype "bidirectional"))
      (node (ref "U1") (pin "4") (pinfunction "GND_4") (pintype "bidirectional"))
      (node (ref "U2") (pin "2") (pinfunction "GND_2") (pintype "bidirectional"))
      (node (ref "U2") (pin "4") (pinfunction "GND_4") (pintype "bidirectional"))
      (node (ref "U3") (pin "10") (pinfunction "AVSS_RFN_10") (pintype "bidirectional"))
      (node (ref "U3") (pin "11") (pinfunction "TEST_11") (pintype "bidirectional"))
      (node (ref "U3") (pin "20") (pinfunction "DVSS_20") (pintype "bidirectional"))
      (node (ref "U3") (pin "24") (pinfunction "DVSS_24") (pintype "bidirectional"))
      (node (ref "U3") (pin "35") (pinfunction "DVSS_35") (pintype "bidirectional"))
      (node (ref "U3") (pin "45") (pinfunction "DVSS_45") (pintype "bidirectional"))
      (node (ref "U3") (pin "55") (pinfunction "DVSS_55") (pintype "bidirectional"))
      (node (ref "U3") (pin "58") (pinfunction "AVSS_58") (pintype "bidirectional"))
      (node (ref "U3") (pin "61") (pinfunction "AVSS_61") (pintype "bidirectional"))
      (node (ref "U3") (pin "7") (pinfunction "AVSS_RFP_7") (pintype "bidirectional"))
      (node (ref "U3") (pin "PAD") (pinfunction "PAD_PAD") (pintype "bidirectional"))
      (node (ref "U4") (pin "16") (pinfunction "GND_16") (pintype "bidirectional"))
      (node (ref "U4") (pin "6") (pinfunction "GND_6") (pintype "bidirectional"))
      (node (ref "U5") (pin "2") (pinfunction "GND_2") (pintype "bidirectional"))
      (node (ref "U6") (pin "3") (pinfunction "GND_3") (pintype "power_in"))
      (node (ref "U7") (pin "2") (pinfunction "VSS_2") (pintype "power_in"))
      (node (ref "USB") (pin "GND") (pinfunction "GND_GND") (pintype "bidirectional"))
      (node (ref "USB") (pin "GND@1") (pinfunction "GND_GND@1") (pintype "bidirectional"))
      (node (ref "USB") (pin "GND@3") (pinfunction "GND_GND@3") (pintype "bidirectional"))
      (node (ref "X1") (pin "2") (pinfunction "2_2") (pintype "passive"))
      (node (ref "X1") (pin "3") (pinfunction "3_3") (pintype "passive"))
    )
    (net (code "26") (name "MISO") (class "Default")
      (node (ref "D3") (pin "3") (pinfunction "Z3_3") (pintype "bidirectional"))
      (node (ref "ICSP") (pin "1") (pinfunction "1_1") (pintype "passive"))
      (node (ref "R16") (pin "2") (pinfunction "2_2") (pintype "passive"))
      (node (ref "U3") (pin "39") (pinfunction "PB3:MISO:PDO:PCINT3_39") (pintype "bidirectional"))
    )
    (net (code "27") (name "MOSI") (class "Default")
      (node (ref "D3") (pin "4") (pinfunction "Z4_4") (pintype "bidirectional"))
      (node (ref "ICSP") (pin "4") (pinfunction "4_4") (pintype "passive"))
      (node (ref "R16") (pin "8") (pinfunction "2_8") (pintype "passive"))
      (node (ref "U3") (pin "38") (pinfunction "PB2:MOSI:PDI:PCINT2_38") (pintype "bidirectional"))
    )
    (net (code "28") (name "Net-(ANALOG-Pad1)") (class "Default")
      (node (ref "ANALOG") (pin "1") (pinfunction "1_1") (pintype "passive"))
      (node (ref "ANALOG-TEST") (pin "1") (pinfunction "1_1") (pintype "passive"))
      (node (ref "R12") (pin "1") (pinfunction "1_1") (pintype "passive"))
    )
    (net (code "29") (name "Net-(ANALOG-Pad5)") (class "Default")
      (node (ref "ANALOG") (pin "5") (pinfunction "5_5") (pintype "passive"))
      (node (ref "ANALOG-TEST") (pin "5") (pinfunction "5_5") (pintype "passive"))
      (node (ref "SDA-J") (pin "2") (pinfunction "2_2") (pintype "passive"))
    )
    (net (code "30") (name "Net-(ANALOG-Pad6)") (class "Default")
      (node (ref "ANALOG") (pin "6") (pinfunction "6_6") (pintype "passive"))
      (node (ref "ANALOG-TEST") (pin "6") (pinfunction "6_6") (pintype "passive"))
      (node (ref "SCL-J") (pin "2") (pinfunction "2_2") (pintype "passive"))
    )
    (net (code "31") (name "Net-(ANT1-PadA)") (class "Default")
      (node (ref "ANT1") (pin "A") (pinfunction "A_A") (pintype "bidirectional"))
      (node (ref "C21") (pin "1") (pinfunction "1_1") (pintype "passive"))
    )
    (net (code "32") (name "Net-(B1-OUT)") (class "Default")
      (node (ref "B1") (pin "1") (pinfunction "OUT_1") (pintype "bidirectional"))
      (node (ref "C11") (pin "2") (pinfunction "2_2") (pintype "passive"))
    )
    (net (code "33") (name "Net-(BATMON-J-Pad1)") (class "Default")
      (node (ref "BATMON-J") (pin "1") (pinfunction "1_1") (pintype "passive"))
      (node (ref "R10") (pin "1") (pinfunction "1_1") (pintype "passive"))
    )
    (net (code "34") (name "Net-(C14-Pad1)") (class "Default")
      (node (ref "C14") (pin "1") (pinfunction "1_1") (pintype "passive"))
      (node (ref "U3") (pin "21") (pinfunction "DVDD_21") (pintype "bidirectional"))
      (node (ref "U3") (pin "22") (pinfunction "DVDD_22") (pintype "bidirectional"))
    )
    (net (code "35") (name "Net-(CHG-PadC)") (class "Default")
      (node (ref "CHG") (pin "C") (pinfunction "C_C") (pintype "passive"))
      (node (ref "R3") (pin "2") (pinfunction "2_2") (pintype "passive"))
    )
    (net (code "36") (name "Net-(D6-Z1)") (class "Default")
      (node (ref "D6") (pin "1") (pinfunction "Z1_1") (pintype "bidirectional"))
      (node (ref "R17") (pin "6") (pinfunction "2_6") (pintype "passive"))
      (node (ref "U3") (pin "26") (pinfunction "PD1:SDA:INT1_26") (pintype "bidirectional"))
    )
    (net (code "37") (name "Net-(D6-Z6)") (class "Default")
      (node (ref "D6") (pin "6") (pinfunction "Z6_6") (pintype "bidirectional"))
      (node (ref "R17") (pin "8") (pinfunction "2_8") (pintype "passive"))
      (node (ref "U3") (pin "25") (pinfunction "PD0:SCL:INT0_25") (pintype "bidirectional"))
    )
    (net (code "38") (name "Net-(D11-J-Pad2)") (class "Default")
      (node (ref "D11-J") (pin "2") (pinfunction "2_2") (pintype "passive"))
      (node (ref "DIGITAL1") (pin "4") (pinfunction "4_4") (pintype "passive"))
      (node (ref "DIGITAL1-TEST") (pin "7") (pinfunction "7_7") (pintype "passive"))
    )
    (net (code "39") (name "Net-(DIGITAL0-Pad1)") (class "Default")
      (node (ref "DIGITAL0") (pin "1") (pinfunction "1_1") (pintype "passive"))
      (node (ref "JP2") (pin "1") (pinfunction "1_1") (pintype "passive"))
      (node (ref "R15") (pin "1") (pinfunction "1_1") (pintype "passive"))
    )
    (net (code "40") (name "Net-(DIGITAL0-Pad5)") (class "Default")
      (node (ref "DIGITAL0") (pin "5") (pinfunction "5_5") (pintype "passive"))
      (node (ref "JP2") (pin "5") (pinfunction "5_5") (pintype "passive"))
      (node (ref "R14") (pin "1") (pinfunction "1_1") (pintype "passive"))
    )
    (net (code "41") (name "Net-(DIGITAL1-Pad5)") (class "Default")
      (node (ref "DIGITAL1") (pin "5") (pinfunction "5_5") (pintype "passive"))
      (node (ref "DIGITAL1-TEST") (pin "6") (pinfunction "6_6") (pintype "passive"))
      (node (ref "R16") (pin "1") (pinfunction "1_1") (pintype "passive"))
    )
    (net (code "42") (name "Net-(J1A-1)") (class "Default")
      (node (ref "C10") (pin "1") (pinfunction "1_1") (pintype "passive"))
      (node (ref "J1") (pin "CENTER") (pinfunction "1_CENTER") (pintype "passive"))
    )
    (net (code "43") (name "Net-(L-PadA)") (class "Default")
      (node (ref "L") (pin "A") (pinfunction "A_A") (pintype "passive"))
      (node (ref "R7") (pin "2") (pinfunction "2_2") (pintype "passive"))
    )
    (net (code "44") (name "Net-(POWER-Pad1)") (class "Default")
      (node (ref "POWER") (pin "1") (pinfunction "1_1") (pintype "passive"))
      (node (ref "POWER-TEST") (pin "1") (pinfunction "1_1") (pintype "passive"))
    )
    (net (code "45") (name "Net-(PWR-LED-J-Pad1)") (class "Default")
      (node (ref "PWR-LED-J") (pin "1") (pinfunction "1_1") (pintype "passive"))
      (node (ref "R6") (pin "1") (pinfunction "1_1") (pintype "passive"))
    )
    (net (code "46") (name "Net-(PWR_LED-PadA)") (class "Default")
      (node (ref "PWR_LED") (pin "A") (pinfunction "A_A") (pintype "passive"))
      (node (ref "R6") (pin "2") (pinfunction "2_2") (pintype "passive"))
    )
    (net (code "47") (name "Net-(R7B-2)") (class "Default")
      (node (ref "R7") (pin "4") (pinfunction "2_4") (pintype "passive"))
      (node (ref "TX") (pin "C") (pinfunction "C_C") (pintype "passive"))
    )
    (net (code "48") (name "Net-(R7D-2)") (class "Default")
      (node (ref "R7") (pin "8") (pinfunction "2_8") (pintype "passive"))
      (node (ref "RX") (pin "C") (pinfunction "C_C") (pintype "passive"))
    )
    (net (code "49") (name "Net-(R8-Pad2)") (class "Default")
      (node (ref "R8") (pin "2") (pinfunction "2_2") (pintype "passive"))
      (node (ref "RFRX") (pin "C") (pinfunction "C_C") (pintype "passive"))
    )
    (net (code "50") (name "Net-(R9-Pad2)") (class "Default")
      (node (ref "R9") (pin "2") (pinfunction "2_2") (pintype "passive"))
      (node (ref "RFTX") (pin "C") (pinfunction "C_C") (pintype "passive"))
    )
    (net (code "51") (name "Net-(R12B-1)") (class "Default")
      (node (ref "ANALOG") (pin "2") (pinfunction "2_2") (pintype "passive"))
      (node (ref "ANALOG-TEST") (pin "2") (pinfunction "2_2") (pintype "passive"))
      (node (ref "R12") (pin "3") (pinfunction "1_3") (pintype "passive"))
    )
    (net (code "52") (name "Net-(R12C-1)") (class "Default")
      (node (ref "ANALOG") (pin "3") (pinfunction "3_3") (pintype "passive"))
      (node (ref "ANALOG-TEST") (pin "3") (pinfunction "3_3") (pintype "passive"))
      (node (ref "R12") (pin "5") (pinfunction "1_5") (pintype "passive"))
    )
    (net (code "53") (name "Net-(R12D-1)") (class "Default")
      (node (ref "ANALOG") (pin "4") (pinfunction "4_4") (pintype "passive"))
      (node (ref "ANALOG-TEST") (pin "4") (pinfunction "4_4") (pintype "passive"))
      (node (ref "R12") (pin "7") (pinfunction "1_7") (pintype "passive"))
    )
    (net (code "54") (name "Net-(R13B-1)") (class "Default")
      (node (ref "DIGITAL1") (pin "1") (pinfunction "1_1") (pintype "passive"))
      (node (ref "DIGITAL1-TEST") (pin "10") (pinfunction "10_10") (pintype "passive"))
      (node (ref "R13") (pin "3") (pinfunction "1_3") (pintype "passive"))
    )
    (net (code "55") (name "Net-(R13C-1)") (class "Default")
      (node (ref "DIGITAL1") (pin "2") (pinfunction "2_2") (pintype "passive"))
      (node (ref "DIGITAL1-TEST") (pin "9") (pinfunction "9_9") (pintype "passive"))
      (node (ref "R13") (pin "5") (pinfunction "1_5") (pintype "passive"))
    )
    (net (code "56") (name "Net-(R13D-1)") (class "Default")
      (node (ref "DIGITAL1") (pin "3") (pinfunction "3_3") (pintype "passive"))
      (node (ref "DIGITAL1-TEST") (pin "8") (pinfunction "8_8") (pintype "passive"))
      (node (ref "R13") (pin "7") (pinfunction "1_7") (pintype "passive"))
    )
    (net (code "57") (name "Net-(R14B-1)") (class "Default")
      (node (ref "DIGITAL0") (pin "6") (pinfunction "6_6") (pintype "passive"))
      (node (ref "JP2") (pin "6") (pinfunction "6_6") (pintype "passive"))
      (node (ref "R14") (pin "3") (pinfunction "1_3") (pintype "passive"))
    )
    (net (code "58") (name "Net-(R14C-1)") (class "Default")
      (node (ref "DIGITAL0") (pin "7") (pinfunction "7_7") (pintype "passive"))
      (node (ref "JP2") (pin "7") (pinfunction "7_7") (pintype "passive"))
      (node (ref "R14") (pin "5") (pinfunction "1_5") (pintype "passive"))
    )
    (net (code "59") (name "Net-(R14D-1)") (class "Default")
      (node (ref "DIGITAL0") (pin "8") (pinfunction "8_8") (pintype "passive"))
      (node (ref "JP2") (pin "8") (pinfunction "8_8") (pintype "passive"))
      (node (ref "R14") (pin "7") (pinfunction "1_7") (pintype "passive"))
    )
    (net (code "60") (name "Net-(R15B-1)") (class "Default")
      (node (ref "DIGITAL0") (pin "2") (pinfunction "2_2") (pintype "passive"))
      (node (ref "JP2") (pin "2") (pinfunction "2_2") (pintype "passive"))
      (node (ref "R15") (pin "3") (pinfunction "1_3") (pintype "passive"))
    )
    (net (code "61") (name "Net-(R15C-1)") (class "Default")
      (node (ref "DIGITAL0") (pin "3") (pinfunction "3_3") (pintype "passive"))
      (node (ref "JP2") (pin "3") (pinfunction "3_3") (pintype "passive"))
      (node (ref "R15") (pin "5") (pinfunction "1_5") (pintype "passive"))
    )
    (net (code "62") (name "Net-(R15D-1)") (class "Default")
      (node (ref "DIGITAL0") (pin "4") (pinfunction "4_4") (pintype "passive"))
      (node (ref "JP2") (pin "4") (pinfunction "4_4") (pintype "passive"))
      (node (ref "R15") (pin "7") (pinfunction "1_7") (pintype "passive"))
    )
    (net (code "63") (name "Net-(R16B-1)") (class "Default")
      (node (ref "D11-J") (pin "3") (pinfunction "3_3") (pintype "passive"))
      (node (ref "R16") (pin "3") (pinfunction "1_3") (pintype "passive"))
    )
    (net (code "64") (name "Net-(R16C-1)") (class "Default")
      (node (ref "DIGITAL1") (pin "6") (pinfunction "6_6") (pintype "passive"))
      (node (ref "DIGITAL1-TEST") (pin "5") (pinfunction "5_5") (pintype "passive"))
      (node (ref "R16") (pin "5") (pinfunction "1_5") (pintype "passive"))
    )
    (net (code "65") (name "Net-(R16D-1)") (class "Default")
      (node (ref "D11-J") (pin "1") (pinfunction "1_1") (pintype "passive"))
      (node (ref "R16") (pin "7") (pinfunction "1_7") (pintype "passive"))
    )
    (net (code "66") (name "Net-(R17-Pad1)") (class "Default")
      (node (ref "R17") (pin "1") (pinfunction "1_1") (pintype "passive"))
      (node (ref "SDA-J") (pin "1") (pinfunction "1_1") (pintype "passive"))
    )
    (net (code "67") (name "Net-(R17B-1)") (class "Default")
      (node (ref "R17") (pin "3") (pinfunction "1_3") (pintype "passive"))
      (node (ref "SCL-J") (pin "1") (pinfunction "1_1") (pintype "passive"))
    )
    (net (code "68") (name "Net-(U3-AVDD)") (class "Default")
      (node (ref "C16") (pin "2") (pinfunction "2_2") (pintype "passive"))
      (node (ref "U3") (pin "60") (pinfunction "AVDD_60") (pintype "bidirectional"))
    )
    (net (code "69") (name "Net-(U3-CLKI)") (class "Default")
      (node (ref "CLKI") (pin "1") (pinfunction "1_1") (pintype "passive"))
      (node (ref "U3") (pin "33") (pinfunction "CLKI_33") (pintype "bidirectional"))
    )
    (net (code "70") (name "Net-(U3-PD5:XCK1)") (class "Default")
      (node (ref "RFTX") (pin "A") (pinfunction "A_A") (pintype "passive"))
      (node (ref "U3") (pin "30") (pinfunction "PD5:XCK1_30") (pintype "bidirectional"))
    )
    (net (code "71") (name "Net-(U3-PD6:T1)") (class "Default")
      (node (ref "RFRX") (pin "A") (pinfunction "A_A") (pintype "passive"))
      (node (ref "U3") (pin "31") (pinfunction "PD6:T1_31") (pintype "bidirectional"))
    )
    (net (code "72") (name "Net-(U3-PG3:TOSC2)") (class "Default")
      (node (ref "C8") (pin "2") (pinfunction "2_2") (pintype "passive"))
      (node (ref "Q2") (pin "2") (pinfunction "2_2") (pintype "passive"))
      (node (ref "U3") (pin "17") (pinfunction "PG3:TOSC2_17") (pintype "bidirectional"))
    )
    (net (code "73") (name "Net-(U3-PG4:TOSC1)") (class "Default")
      (node (ref "C22") (pin "2") (pinfunction "2_2") (pintype "passive"))
      (node (ref "Q2") (pin "1") (pinfunction "1_1") (pintype "passive"))
      (node (ref "U3") (pin "18") (pinfunction "PG4:TOSC1_18") (pintype "bidirectional"))
    )
    (net (code "74") (name "Net-(U3-XTAL1)") (class "Default")
      (node (ref "C2") (pin "2") (pinfunction "2_2") (pintype "passive"))
      (node (ref "Q1") (pin "2") (pinfunction "2_2") (pintype "passive"))
      (node (ref "U3") (pin "56") (pinfunction "XTAL1_56") (pintype "bidirectional"))
    )
    (net (code "75") (name "Net-(U3-XTAL2)") (class "Default")
      (node (ref "C1") (pin "2") (pinfunction "2_2") (pintype "passive"))
      (node (ref "Q1") (pin "1") (pinfunction "1_1") (pintype "passive"))
      (node (ref "U3") (pin "57") (pinfunction "XTAL2_57") (pintype "bidirectional"))
    )
    (net (code "76") (name "Net-(U4-3V3OUT)") (class "Default")
      (node (ref "C17") (pin "1") (pinfunction "1_1") (pintype "passive"))
      (node (ref "U4") (pin "13") (pinfunction "3V3OUT_13") (pintype "bidirectional"))
      (node (ref "U4") (pin "14") (pinfunction "RESET#_14") (pintype "bidirectional"))
      (node (ref "U4") (pin "3") (pinfunction "VCCIO_3") (pintype "bidirectional"))
    )
    (net (code "77") (name "Net-(U4-USBDM)") (class "Default")
      (node (ref "R4") (pin "2") (pinfunction "2_2") (pintype "passive"))
      (node (ref "U4") (pin "12") (pinfunction "USBDM_12") (pintype "bidirectional"))
    )
    (net (code "78") (name "Net-(U4-USBDP)") (class "Default")
      (node (ref "R5") (pin "2") (pinfunction "2_2") (pintype "passive"))
      (node (ref "U4") (pin "11") (pinfunction "USBDP_11") (pintype "bidirectional"))
    )
    (net (code "79") (name "Net-(U4-VCC)") (class "Default")
      (node (ref "L1") (pin "2") (pinfunction "2_2") (pintype "passive"))
      (node (ref "U4") (pin "15") (pinfunction "VCC_15") (pintype "bidirectional"))
    )
    (net (code "80") (name "Net-(U5-J1)") (class "Default")
      (node (ref "C11") (pin "1") (pinfunction "1_1") (pintype "passive"))
      (node (ref "U5") (pin "5") (pinfunction "J1_5") (pintype "bidirectional"))
    )
    (net (code "81") (name "Net-(U5-J2)") (class "Default")
      (node (ref "C10") (pin "2") (pinfunction "2_2") (pintype "passive"))
      (node (ref "U5") (pin "3") (pinfunction "J2_3") (pintype "bidirectional"))
    )
    (net (code "82") (name "Net-(U5-J3)") (class "Default")
      (node (ref "C21") (pin "2") (pinfunction "2_2") (pintype "passive"))
      (node (ref "U5") (pin "1") (pinfunction "J3_1") (pintype "bidirectional"))
    )
    (net (code "83") (name "Net-(U5-V1)") (class "Default")
      (node (ref "ANT-J2") (pin "2") (pinfunction "2_2") (pintype "passive"))
      (node (ref "U5") (pin "4") (pinfunction "V1_4") (pintype "bidirectional"))
    )
    (net (code "84") (name "Net-(U5-V2)") (class "Default")
      (node (ref "ANT-J1") (pin "2") (pinfunction "2_2") (pintype "passive"))
      (node (ref "U5") (pin "6") (pinfunction "V2_6") (pintype "bidirectional"))
    )
    (net (code "85") (name "Net-(U7-PROG)") (class "Default")
      (node (ref "R2") (pin "2") (pinfunction "2_2") (pintype "passive"))
      (node (ref "U7") (pin "5") (pinfunction "PROG_5") (pintype "input"))
    )
    (net (code "86") (name "Net-(U7-STAT)") (class "Default")
      (node (ref "R3") (pin "1") (pinfunction "1_1") (pintype "passive"))
      (node (ref "U7") (pin "1") (pinfunction "STAT_1") (pintype "output"))
    )
    (net (code "87") (name "PB0") (class "Default")
      (node (ref "AUX") (pin "2") (pinfunction "2_2") (pintype "passive"))
      (node (ref "AUX-TEST") (pin "2") (pinfunction "2_2") (pintype "passive"))
      (node (ref "U3") (pin "36") (pinfunction "PB0:SSN:PCINT0_36") (pintype "bidirectional"))
    )
    (net (code "88") (name "PD4") (class "Default")
      (node (ref "AUX") (pin "4") (pinfunction "4_4") (pintype "passive"))
      (node (ref "AUX-TEST") (pin "4") (pinfunction "4_4") (pintype "passive"))
      (node (ref "U3") (pin "29") (pinfunction "PD4:ICP1_29") (pintype "bidirectional"))
    )
    (net (code "89") (name "PD7") (class "Default")
      (node (ref "AUX") (pin "1") (pinfunction "1_1") (pintype "passive"))
      (node (ref "AUX-TEST") (pin "1") (pinfunction "1_1") (pintype "passive"))
      (node (ref "U3") (pin "32") (pinfunction "PD7:T0_32") (pintype "bidirectional"))
    )
    (net (code "90") (name "PG2") (class "Default")
      (node (ref "AUX") (pin "6") (pinfunction "6_6") (pintype "passive"))
      (node (ref "AUX-TEST") (pin "6") (pinfunction "6_6") (pintype "passive"))
      (node (ref "U3") (pin "16") (pinfunction "PG2:AMR_16") (pintype "bidirectional"))
    )
    (net (code "91") (name "PG5") (class "Default")
      (node (ref "AUX") (pin "3") (pinfunction "3_3") (pintype "passive"))
      (node (ref "AUX-TEST") (pin "3") (pinfunction "3_3") (pintype "passive"))
      (node (ref "U3") (pin "19") (pinfunction "PG5:OC0B_19") (pintype "bidirectional"))
    )
    (net (code "92") (name "PWRIN") (class "Default")
      (node (ref "D1") (pin "A") (pinfunction "A_A") (pintype "passive"))
      (node (ref "X1") (pin "1A") (pinfunction "1A_1A") (pintype "passive"))
      (node (ref "X1") (pin "1B") (pinfunction "1B_1B") (pintype "passive"))
    )
    (net (code "93") (name "RESET") (class "Default")
      (node (ref "C9") (pin "2") (pinfunction "2_2") (pintype "passive"))
      (node (ref "ICSP") (pin "5") (pinfunction "5_5") (pintype "passive"))
      (node (ref "POWER") (pin "3") (pinfunction "3_3") (pintype "passive"))
      (node (ref "POWER-TEST") (pin "3") (pinfunction "3_3") (pintype "passive"))
      (node (ref "R1") (pin "1") (pinfunction "1_1") (pintype "passive"))
      (node (ref "SW1") (pin "A") (pinfunction "A_A") (pintype "bidirectional"))
      (node (ref "SW1") (pin "A'") (pinfunction "A'_A'") (pintype "bidirectional"))
      (node (ref "U6") (pin "2") (pinfunction "I_2") (pintype "input"))
    )
    (net (code "94") (name "RFN") (class "Default")
      (node (ref "B1") (pin "3") (pinfunction "BAL1_3") (pintype "bidirectional"))
      (node (ref "U3") (pin "9") (pinfunction "RFN_9") (pintype "bidirectional"))
    )
    (net (code "95") (name "RFP") (class "Default")
      (node (ref "B1") (pin "4") (pinfunction "BAL2_4") (pintype "bidirectional"))
      (node (ref "U3") (pin "8") (pinfunction "RFP_8") (pintype "bidirectional"))
    )
    (net (code "96") (name "RST") (class "Default")
      (node (ref "U3") (pin "12") (pinfunction "~{RESET}_12") (pintype "bidirectional"))
      (node (ref "U6") (pin "4") (pinfunction "O_4") (pintype "output"))
    )
    (net (code "97") (name "RXD0") (class "Default")
      (node (ref "U3") (pin "46") (pinfunction "PE0:RXD0:PCINT8_46") (pintype "bidirectional"))
      (node (ref "U4") (pin "20") (pinfunction "TXD_20") (pintype "bidirectional"))
      (node (ref "UART0") (pin "1") (pinfunction "1_1") (pintype "passive"))
    )
    (net (code "98") (name "RXD1") (class "Default")
      (node (ref "D5") (pin "3") (pinfunction "Z3_3") (pintype "bidirectional"))
      (node (ref "R15") (pin "2") (pinfunction "2_2") (pintype "passive"))
      (node (ref "U3") (pin "27") (pinfunction "PD2:RXD1:INT2_27") (pintype "bidirectional"))
    )
    (net (code "99") (name "RXLED") (class "Default")
      (node (ref "R7") (pin "7") (pinfunction "1_7") (pintype "passive"))
      (node (ref "U4") (pin "17") (pinfunction "CBUS1_17") (pintype "bidirectional"))
    )
    (net (code "100") (name "SCK") (class "Default")
      (node (ref "D3") (pin "6") (pinfunction "Z6_6") (pintype "bidirectional"))
      (node (ref "ICSP") (pin "3") (pinfunction "3_3") (pintype "passive"))
      (node (ref "R16") (pin "6") (pinfunction "2_6") (pintype "passive"))
      (node (ref "R7") (pin "1") (pinfunction "1_1") (pintype "passive"))
      (node (ref "U3") (pin "37") (pinfunction "PB1:SCK:PCINT1_37") (pintype "bidirectional"))
    )
    (net (code "101") (name "SCL") (class "Default")
      (node (ref "DIGITAL1") (pin "10") (pinfunction "10_10") (pintype "passive"))
      (node (ref "DIGITAL1-TEST") (pin "1") (pinfunction "1_1") (pintype "passive"))
      (node (ref "R17") (pin "7") (pinfunction "1_7") (pintype "passive"))
      (node (ref "SCL-J") (pin "3") (pinfunction "3_3") (pintype "passive"))
    )
    (net (code "102") (name "SDA") (class "Default")
      (node (ref "DIGITAL1") (pin "9") (pinfunction "9_9") (pintype "passive"))
      (node (ref "DIGITAL1-TEST") (pin "2") (pinfunction "2_2") (pintype "passive"))
      (node (ref "R17") (pin "5") (pinfunction "1_5") (pintype "passive"))
      (node (ref "SDA-J") (pin "3") (pinfunction "3_3") (pintype "passive"))
    )
    (net (code "103") (name "TXD0") (class "Default")
      (node (ref "U3") (pin "47") (pinfunction "PE1:TXD0_47") (pintype "bidirectional"))
      (node (ref "U4") (pin "4") (pinfunction "RXD_4") (pintype "bidirectional"))
      (node (ref "UART0") (pin "2") (pinfunction "2_2") (pintype "passive"))
    )
    (net (code "104") (name "TXD1") (class "Default")
      (node (ref "D5") (pin "1") (pinfunction "Z1_1") (pintype "bidirectional"))
      (node (ref "R15") (pin "4") (pinfunction "2_4") (pintype "passive"))
      (node (ref "U3") (pin "28") (pinfunction "PD3:TXD1:INT3_28") (pintype "bidirectional"))
    )
    (net (code "105") (name "TXLED") (class "Default")
      (node (ref "R7") (pin "3") (pinfunction "1_3") (pintype "passive"))
      (node (ref "U4") (pin "10") (pinfunction "CBUS2_10") (pintype "bidirectional"))
    )
    (net (code "106") (name "USBVCC") (class "Default")
      (node (ref "C20") (pin "1") (pinfunction "1_1") (pintype "passive"))
      (node (ref "D15") (pin "A") (pinfunction "A_A") (pintype "passive"))
      (node (ref "F2") (pin "1") (pinfunction "1_1") (pintype "passive"))
      (node (ref "L1") (pin "1") (pinfunction "1_1") (pintype "passive"))
    )
    (net (code "107") (name "USB_5V") (class "Default")
      (node (ref "F2") (pin "2") (pinfunction "2_2") (pintype "passive"))
      (node (ref "USB") (pin "VBUS") (pinfunction "VBUS_VBUS") (pintype "bidirectional"))
      (node (ref "USB_TEST") (pin "3") (pinfunction "3_3") (pintype "passive"))
    )
    (net (code "108") (name "USB_N") (class "Default")
      (node (ref "C19") (pin "1") (pinfunction "1_1") (pintype "passive"))
      (node (ref "R4") (pin "1") (pinfunction "1_1") (pintype "passive"))
      (node (ref "USB") (pin "D-") (pinfunction "D-_D-") (pintype "bidirectional"))
      (node (ref "USB_TEST") (pin "1") (pinfunction "1_1") (pintype "passive"))
    )
    (net (code "109") (name "USB_P") (class "Default")
      (node (ref "C18") (pin "1") (pinfunction "1_1") (pintype "passive"))
      (node (ref "R5") (pin "1") (pinfunction "1_1") (pintype "passive"))
      (node (ref "USB") (pin "D+") (pinfunction "D+_D+") (pintype "bidirectional"))
      (node (ref "USB_TEST") (pin "2") (pinfunction "2_2") (pintype "passive"))
    )
    (net (code "110") (name "VBAT") (class "Default")
      (node (ref "BAT") (pin "2") (pinfunction "2_2") (pintype "passive"))
      (node (ref "BATMON-J") (pin "2") (pinfunction "2_2") (pintype "passive"))
      (node (ref "C3") (pin "1") (pinfunction "1_1") (pintype "passive"))
      (node (ref "CHG") (pin "A") (pinfunction "A_A") (pintype "passive"))
      (node (ref "D14") (pin "A") (pinfunction "A_A") (pintype "passive"))
      (node (ref "U7") (pin "3") (pinfunction "VBAT_3") (pintype "power_in"))
      (node (ref "USB_TEST") (pin "4") (pinfunction "4_4") (pintype "passive"))
    )
    (net (code "111") (name "VIN") (class "Default")
      (node (ref "C4") (pin "1") (pinfunction "1_1") (pintype "passive"))
      (node (ref "D1") (pin "C") (pinfunction "C_C") (pintype "passive"))
      (node (ref "POWER") (pin "8") (pinfunction "8_8") (pintype "passive"))
      (node (ref "POWER-TEST") (pin "8") (pinfunction "8_8") (pintype "passive"))
      (node (ref "U1") (pin "1") (pinfunction "IN_1") (pintype "bidirectional"))
    )
    (net (code "112") (name "unconnected-(D2-Z6-Pad6)") (class "Default")
      (node (ref "D2") (pin "6") (pinfunction "Z6_6") (pintype "bidirectional"))
    )
    (net (code "113") (name "unconnected-(D6-Z3-Pad3)") (class "Default")
      (node (ref "D6") (pin "3") (pinfunction "Z3_3") (pintype "bidirectional"))
    )
    (net (code "114") (name "unconnected-(D6-Z4-Pad4)") (class "Default")
      (node (ref "D6") (pin "4") (pinfunction "Z4_4") (pintype "bidirectional"))
    )
    (net (code "115") (name "unconnected-(U3-~{RESET_OUT}-Pad13)") (class "Default")
      (node (ref "U3") (pin "13") (pinfunction "~{RESET_OUT}_13") (pintype "bidirectional"))
    )
    (net (code "116") (name "unconnected-(U4-CBUS0-Pad18)") (class "Default")
      (node (ref "U4") (pin "18") (pinfunction "CBUS0_18") (pintype "bidirectional"))
    )
    (net (code "117") (name "unconnected-(U4-CBUS3-Pad19)") (class "Default")
      (node (ref "U4") (pin "19") (pinfunction "CBUS3_19") (pintype "bidirectional"))
    )
    (net (code "118") (name "unconnected-(U4-CTS#-Pad9)") (class "Default")
      (node (ref "U4") (pin "9") (pinfunction "CTS#_9") (pintype "bidirectional"))
    )
    (net (code "119") (name "unconnected-(U4-DCD#-Pad8)") (class "Default")
      (node (ref "U4") (pin "8") (pinfunction "DCD#_8") (pintype "bidirectional"))
    )
    (net (code "120") (name "unconnected-(U4-DSR#-Pad7)") (class "Default")
      (node (ref "U4") (pin "7") (pinfunction "DSR#_7") (pintype "bidirectional"))
    )
    (net (code "121") (name "unconnected-(U4-RI#-Pad5)") (class "Default")
      (node (ref "U4") (pin "5") (pinfunction "RI#_5") (pintype "bidirectional"))
    )
    (net (code "122") (name "unconnected-(U4-RTS#-Pad2)") (class "Default")
      (node (ref "U4") (pin "2") (pinfunction "RTS#_2") (pintype "bidirectional"))
    )
  )
)
